# v3s-v0_1_1.net
KiCad netlist of a schematic drawn in EAGLE
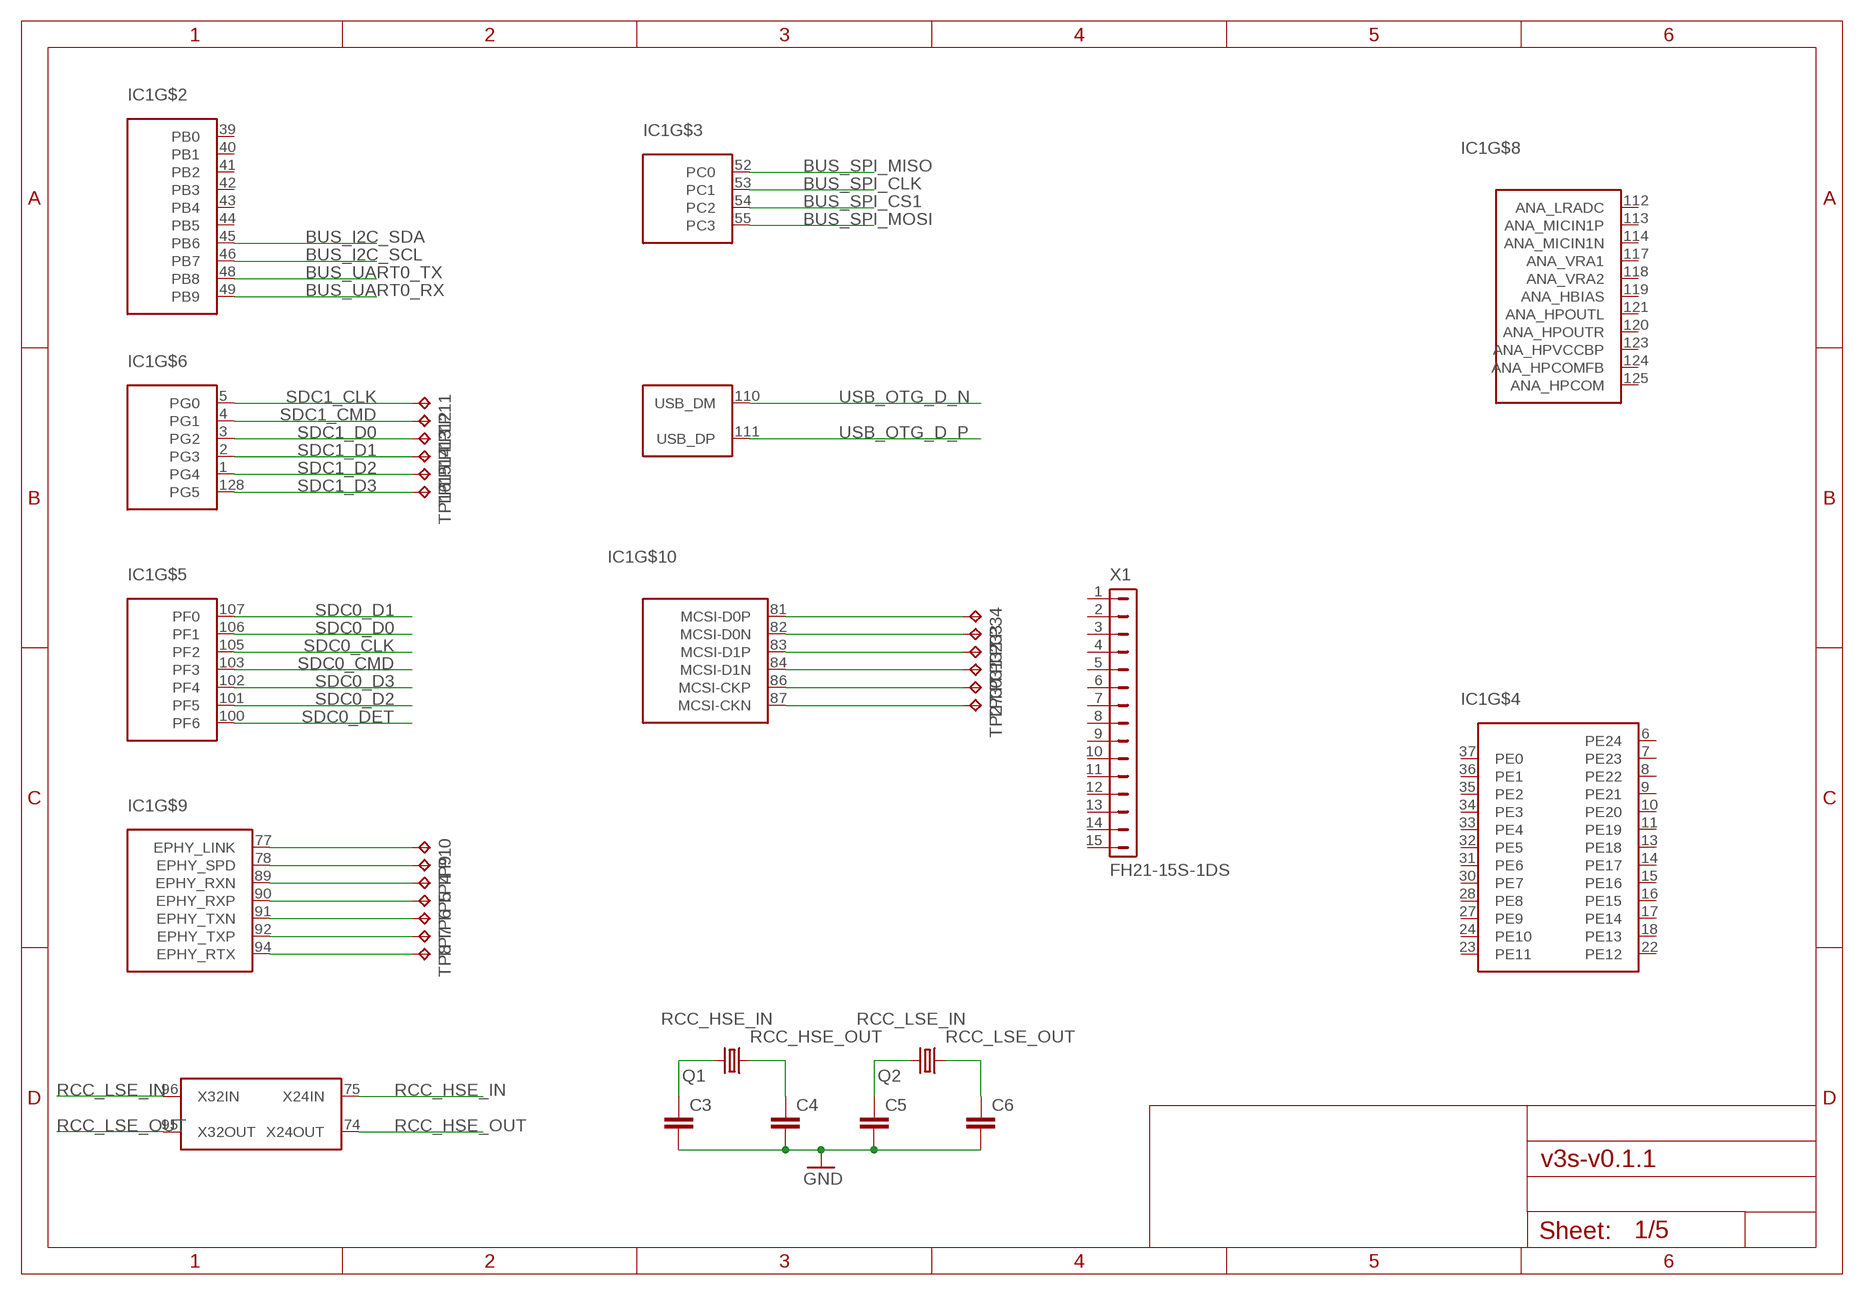
[diagram p0: schematic, sheet 1]
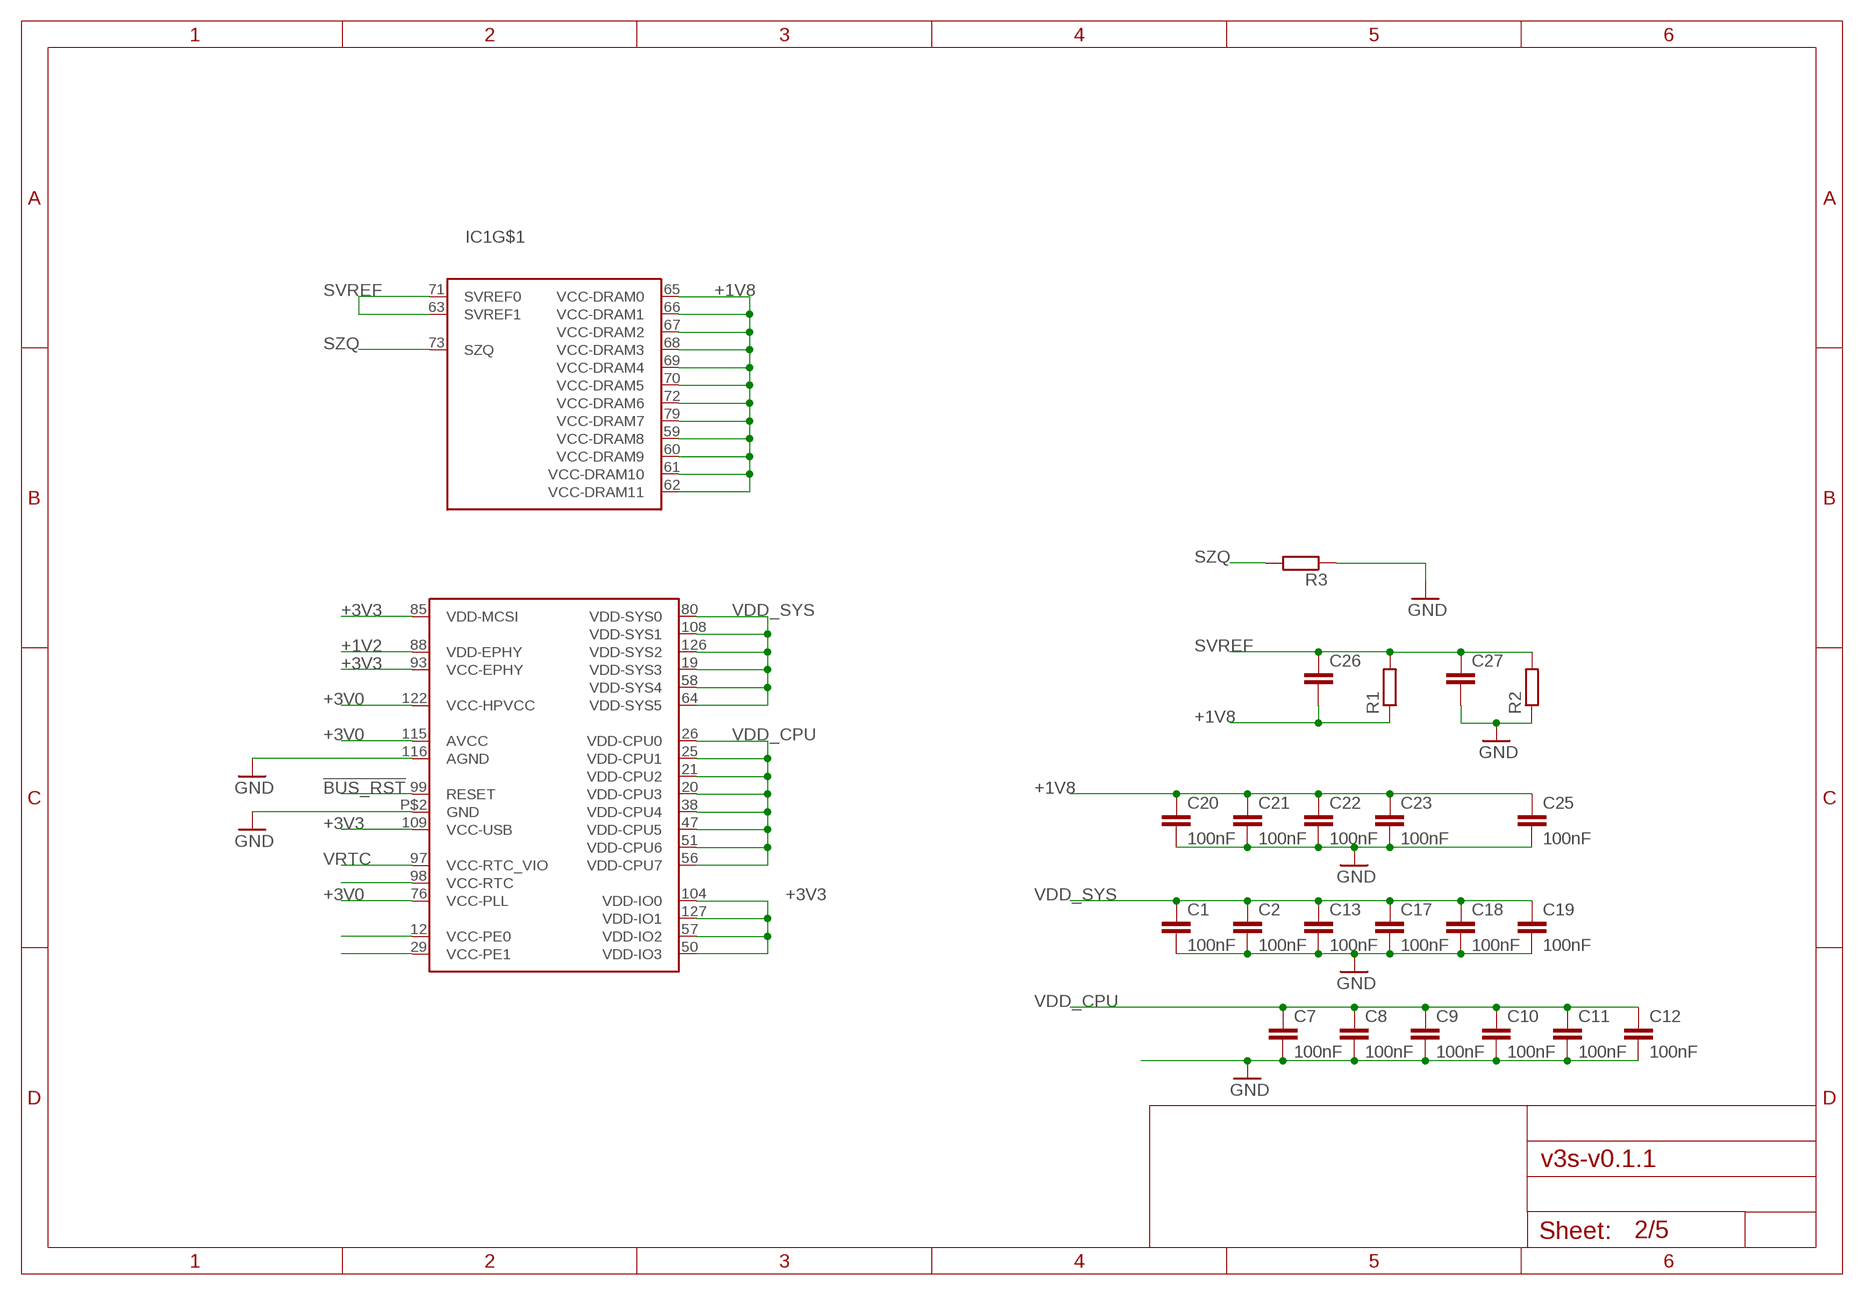
[diagram p1: schematic, sheet 2]
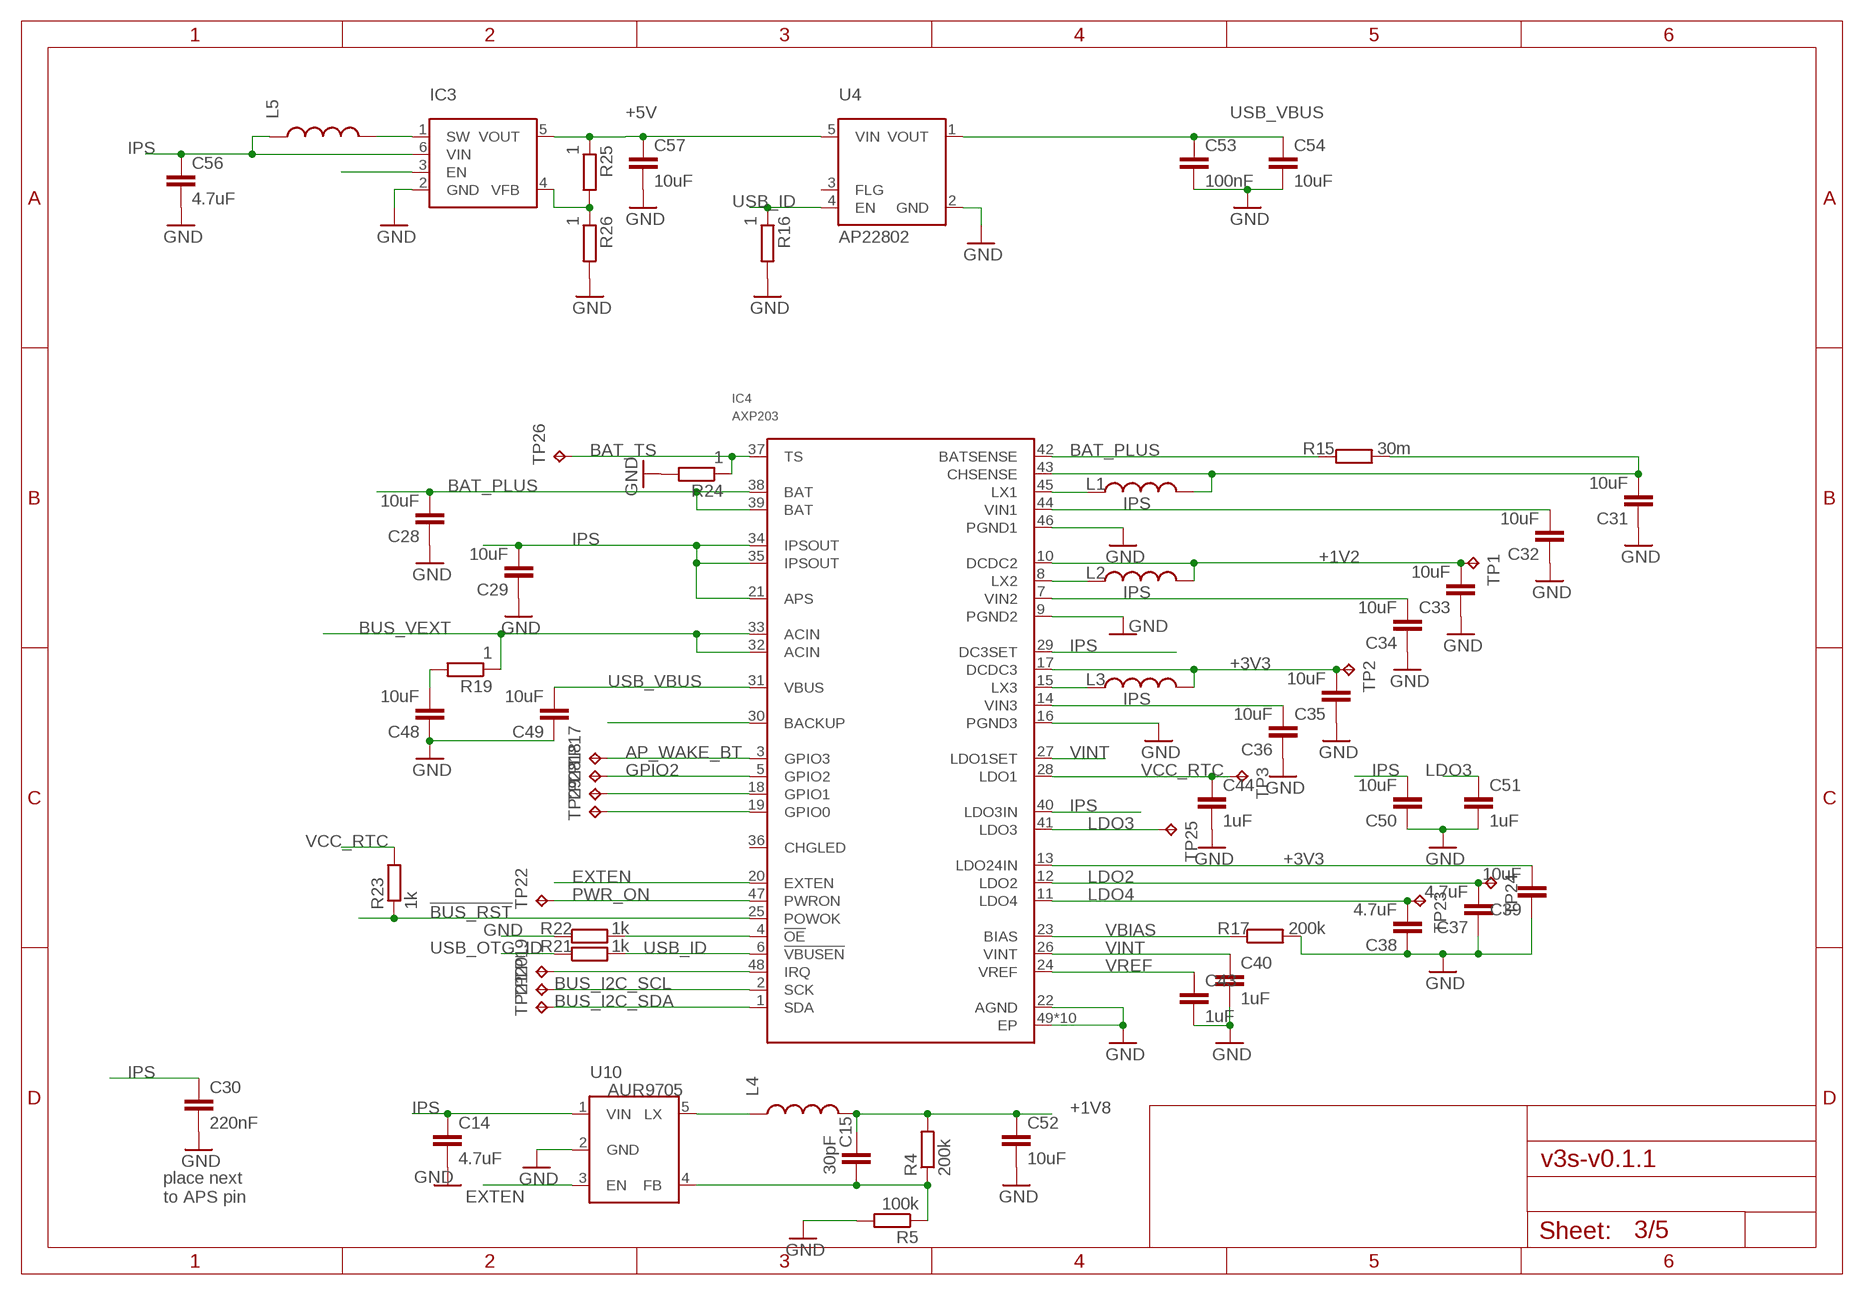
[diagram p2: schematic, sheet 3]
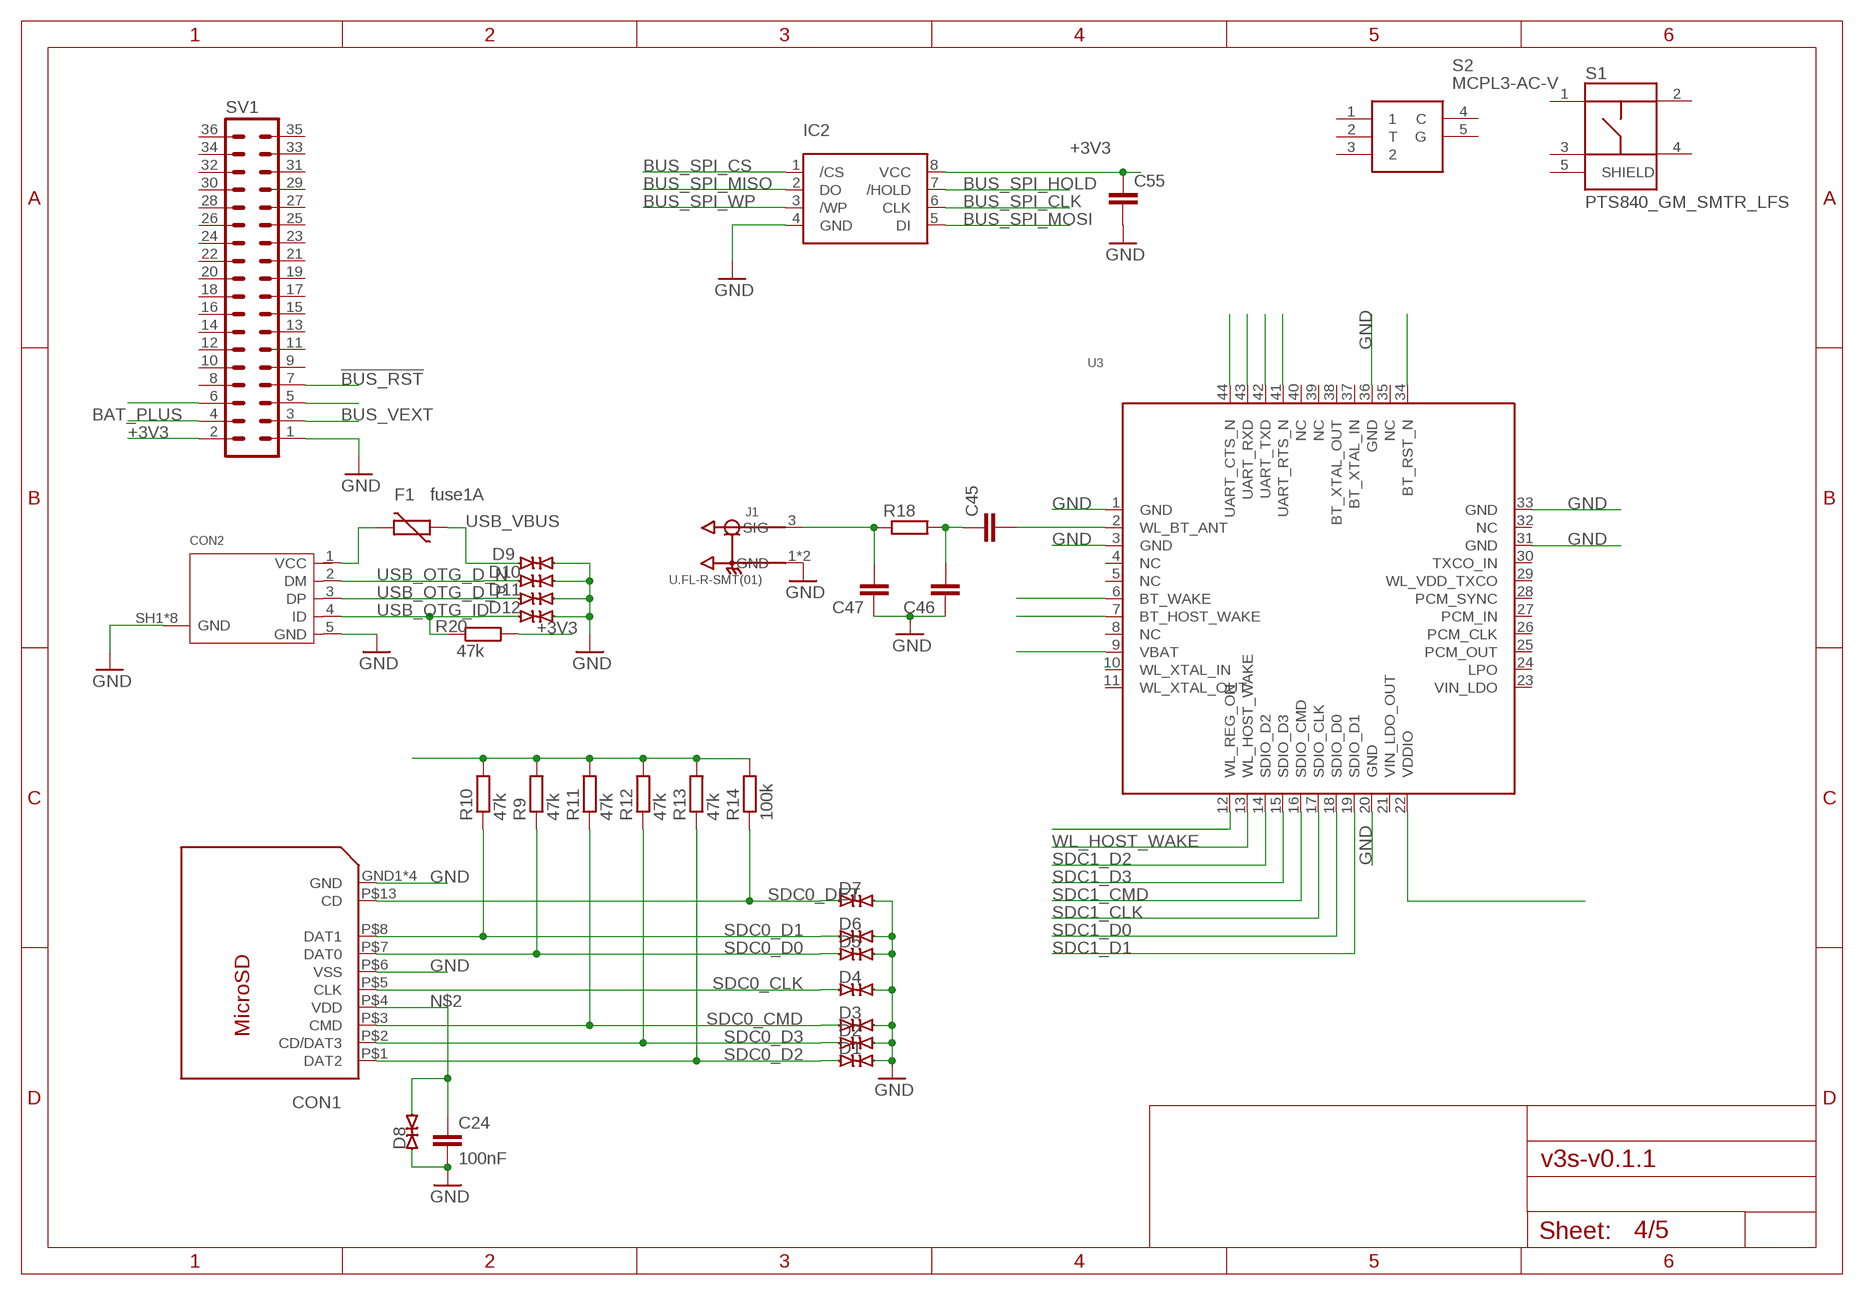
[diagram p3: schematic, sheet 4]
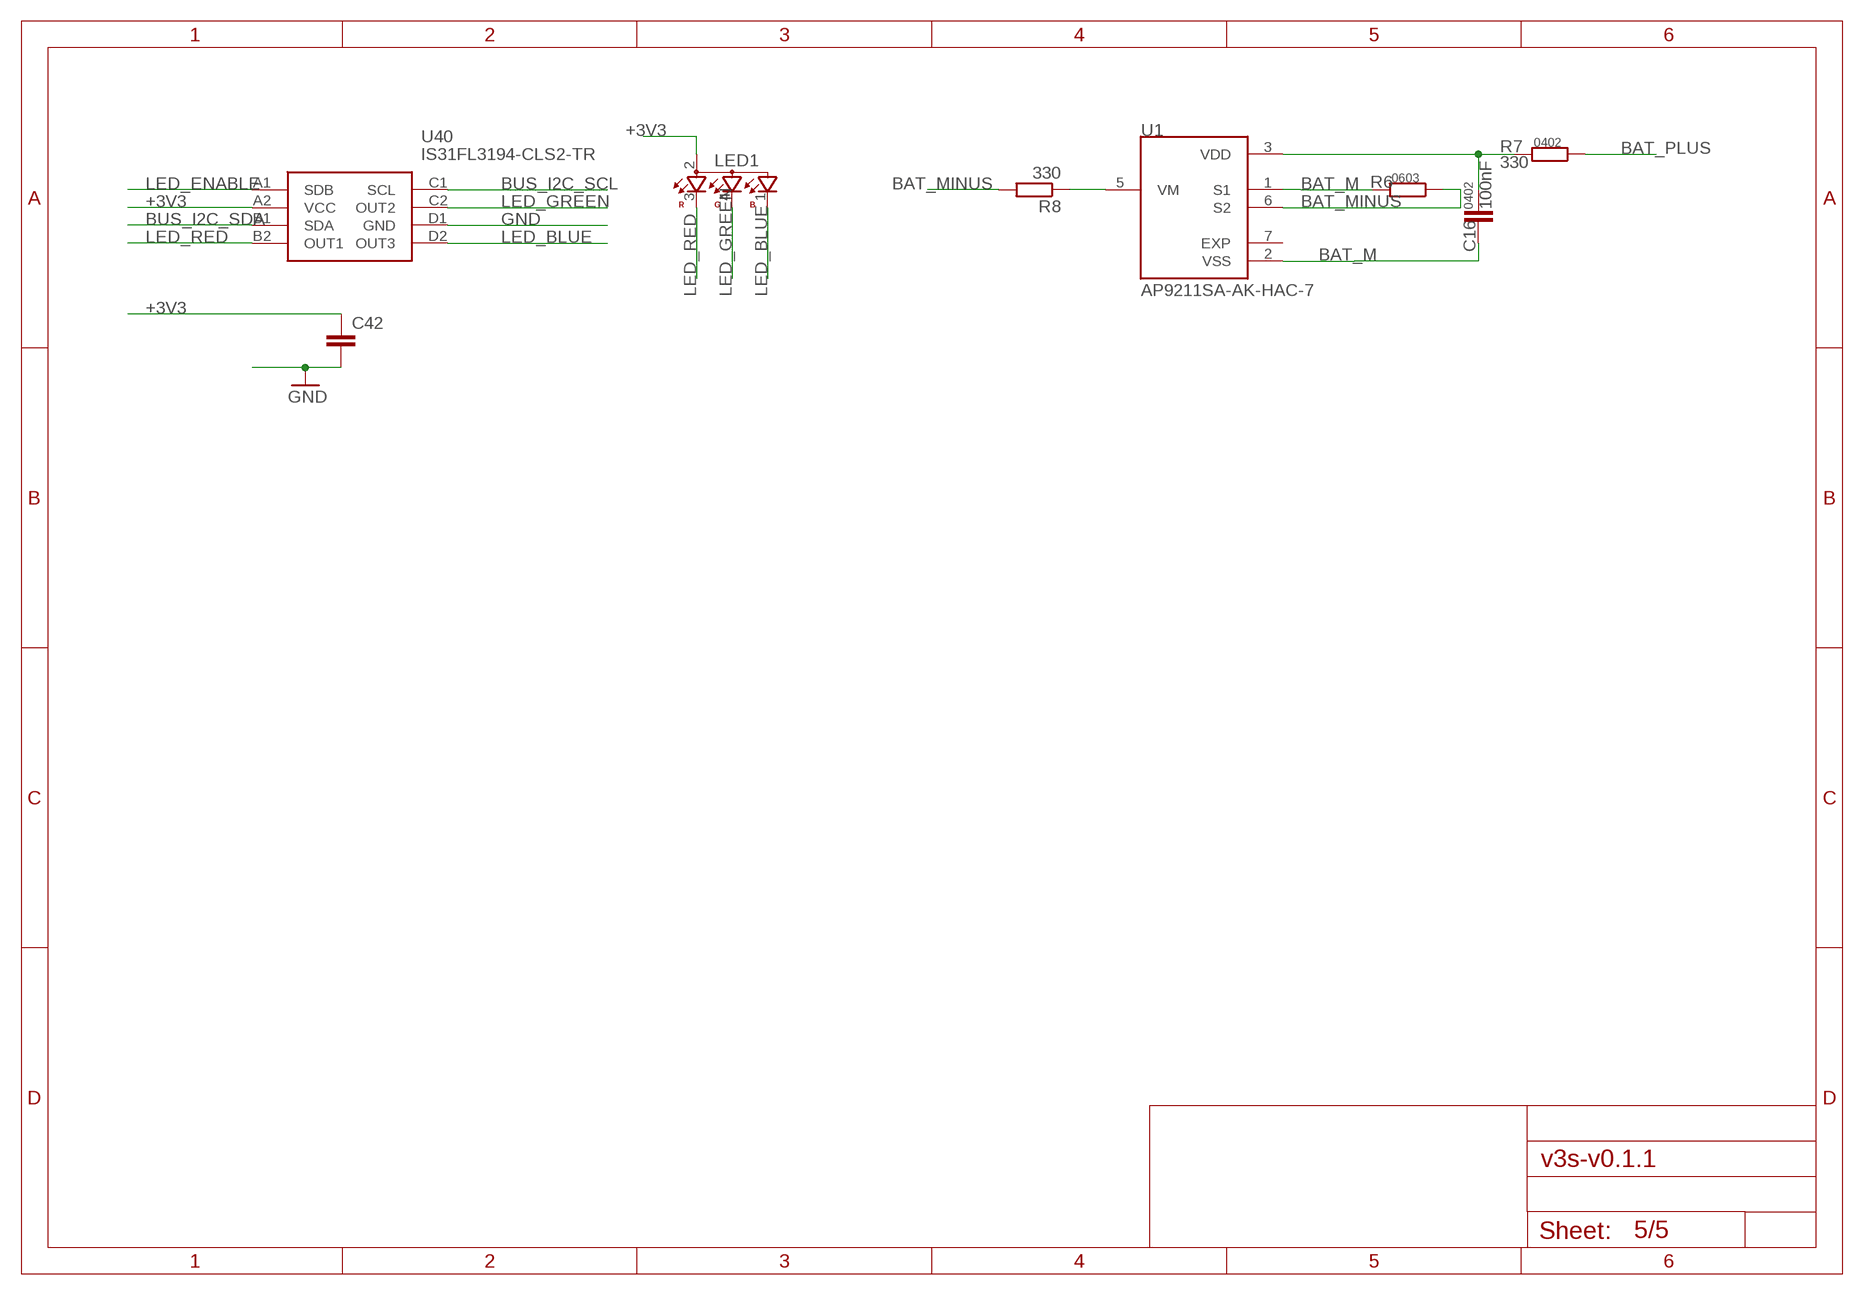
[diagram p4: schematic, sheet 5]

(export (version "E")
  (design (tool "Eeschema 10.0.6"))
  (components
    (comp (ref "C24")
      (value "100nF")
      (footprint "eagle-import:C0402")
      (libsource (lib "eagle-import") (part "C-EUC0402"))
    )
    (comp (ref "C45")
      (value "C-EUC0402")
      (footprint "eagle-import:C0402")
      (libsource (lib "eagle-import") (part "C-EUC0402"))
    )
    (comp (ref "C46")
      (value "C-EUC0402")
      (footprint "eagle-import:C0402")
      (libsource (lib "eagle-import") (part "C-EUC0402"))
    )
    (comp (ref "C47")
      (value "C-EUC0402")
      (footprint "eagle-import:C0402")
      (libsource (lib "eagle-import") (part "C-EUC0402"))
    )
    (comp (ref "C55")
      (value "C-EUC0603")
      (footprint "eagle-import:C0603")
      (libsource (lib "eagle-import") (part "C-EUC0603"))
    )
    (comp (ref "CON1")
      (value "112J-TXAR")
      (footprint "eagle-import:112J")
      (libsource (lib "eagle-import") (part "112J-TXAR"))
    )
    (comp (ref "CON2")
      (value "10118194-0001LF")
      (footprint "eagle-import:10118194")
      (libsource (lib "eagle-import") (part "10118194-0001LF"))
    )
    (comp (ref "D1")
      (value "ESD9B5.0ST5G")
      (footprint "eagle-import:SOD1006X40")
      (libsource (lib "eagle-import") (part "ESD9B5.0ST5G"))
    )
    (comp (ref "D2")
      (value "ESD9B5.0ST5G")
      (footprint "eagle-import:SOD1006X40")
      (libsource (lib "eagle-import") (part "ESD9B5.0ST5G"))
    )
    (comp (ref "D3")
      (value "ESD9B5.0ST5G")
      (footprint "eagle-import:SOD1006X40")
      (libsource (lib "eagle-import") (part "ESD9B5.0ST5G"))
    )
    (comp (ref "D4")
      (value "ESD9B5.0ST5G")
      (footprint "eagle-import:SOD1006X40")
      (libsource (lib "eagle-import") (part "ESD9B5.0ST5G"))
    )
    (comp (ref "D5")
      (value "ESD9B5.0ST5G")
      (footprint "eagle-import:SOD1006X40")
      (libsource (lib "eagle-import") (part "ESD9B5.0ST5G"))
    )
    (comp (ref "D6")
      (value "ESD9B5.0ST5G")
      (footprint "eagle-import:SOD1006X40")
      (libsource (lib "eagle-import") (part "ESD9B5.0ST5G"))
    )
    (comp (ref "D7")
      (value "ESD9B5.0ST5G")
      (footprint "eagle-import:SOD1006X40")
      (libsource (lib "eagle-import") (part "ESD9B5.0ST5G"))
    )
    (comp (ref "D8")
      (value "ESD9B5.0ST5G")
      (footprint "eagle-import:SOD1006X40")
      (libsource (lib "eagle-import") (part "ESD9B5.0ST5G"))
    )
    (comp (ref "D9")
      (value "ESD9B5.0ST5G")
      (footprint "eagle-import:SOD1006X40")
      (libsource (lib "eagle-import") (part "ESD9B5.0ST5G"))
    )
    (comp (ref "D10")
      (value "ESD9B5.0ST5G")
      (footprint "eagle-import:SOD1006X40")
      (libsource (lib "eagle-import") (part "ESD9B5.0ST5G"))
    )
    (comp (ref "D11")
      (value "ESD9B5.0ST5G")
      (footprint "eagle-import:SOD1006X40")
      (libsource (lib "eagle-import") (part "ESD9B5.0ST5G"))
    )
    (comp (ref "D12")
      (value "ESD9B5.0ST5G")
      (footprint "eagle-import:SOD1006X40")
      (libsource (lib "eagle-import") (part "ESD9B5.0ST5G"))
    )
    (comp (ref "F1")
      (value "fuse1A")
      (footprint "eagle-import:CT_CN0603")
      (libsource (lib "eagle-import") (part "VARISTORCN0603"))
    )
    (comp (ref "IC2")
      (value "W25Q128JV")
      (footprint "eagle-import:SO08-208")
      (libsource (lib "eagle-import") (part "W25Q128JV"))
    )
    (comp (ref "J1")
      (value "U.FL-R-SMT(01)")
      (footprint "eagle-import:HRS_U.FL-R-SMT(01)")
      (fields (field (name "MF") "Hirose") (field (name "MP") "U.FL-R-SMT_01_"))
      (libsource (lib "eagle-import") (part "U.FL-R-SMT(01)"))
    )
    (comp (ref "R9")
      (value "47k")
      (footprint "eagle-import:R0402")
      (libsource (lib "eagle-import") (part "R-EU_R0402"))
    )
    (comp (ref "R10")
      (value "47k")
      (footprint "eagle-import:R0402")
      (libsource (lib "eagle-import") (part "R-EU_R0402"))
    )
    (comp (ref "R11")
      (value "47k")
      (footprint "eagle-import:R0402")
      (libsource (lib "eagle-import") (part "R-EU_R0402"))
    )
    (comp (ref "R12")
      (value "47k")
      (footprint "eagle-import:R0402")
      (libsource (lib "eagle-import") (part "R-EU_R0402"))
    )
    (comp (ref "R13")
      (value "47k")
      (footprint "eagle-import:R0402")
      (libsource (lib "eagle-import") (part "R-EU_R0402"))
    )
    (comp (ref "R14")
      (value "100k")
      (footprint "eagle-import:R0402")
      (libsource (lib "eagle-import") (part "R-EU_R0402"))
    )
    (comp (ref "R18")
      (value "R-EU_R0402")
      (footprint "eagle-import:R0402")
      (libsource (lib "eagle-import") (part "R-EU_R0402"))
    )
    (comp (ref "R20")
      (value "47k")
      (footprint "eagle-import:R0402")
      (libsource (lib "eagle-import") (part "R-EU_R0402"))
    )
    (comp (ref "S1")
      (value "PTS840_GM_SMTR_LFS")
      (footprint "eagle-import:SW_PTS840GMSMTRLFS")
      (fields (field (name "MF") "C&K") (field (name "MP") "PTS840 GM SMTR LFS"))
      (libsource (lib "eagle-import") (part "PTS840_GM_SMTR_LFS"))
    )
    (comp (ref "S2")
      (value "MCPL3-AC-V")
      (footprint "eagle-import:MCPL3-AC-V")
      (libsource (lib "eagle-import") (part "MCPL3-AC-V"))
    )
    (comp (ref "SV1")
      (value "MA18-2")
      (footprint "eagle-import:MA18-2")
      (libsource (lib "eagle-import") (part "MA18-2"))
    )
    (comp (ref "U3")
      (value "RTL8723BS")
      (footprint "eagle-import:QFN90P1200X1200X100-44")
      (libsource (lib "eagle-import") (part "RTL8723BS"))
    )
    (comp (ref "C1")
      (value "100nF")
      (footprint "eagle-import:C0402")
      (libsource (lib "eagle-import") (part "C-EUC0402"))
    )
    (comp (ref "C2")
      (value "100nF")
      (footprint "eagle-import:C0402")
      (libsource (lib "eagle-import") (part "C-EUC0402"))
    )
    (comp (ref "C7")
      (value "100nF")
      (footprint "eagle-import:C0402")
      (libsource (lib "eagle-import") (part "C-EUC0402"))
    )
    (comp (ref "C8")
      (value "100nF")
      (footprint "eagle-import:C0402")
      (libsource (lib "eagle-import") (part "C-EUC0402"))
    )
    (comp (ref "C9")
      (value "100nF")
      (footprint "eagle-import:C0402")
      (libsource (lib "eagle-import") (part "C-EUC0402"))
    )
    (comp (ref "C10")
      (value "100nF")
      (footprint "eagle-import:C0402")
      (libsource (lib "eagle-import") (part "C-EUC0402"))
    )
    (comp (ref "C11")
      (value "100nF")
      (footprint "eagle-import:C0402")
      (libsource (lib "eagle-import") (part "C-EUC0402"))
    )
    (comp (ref "C12")
      (value "100nF")
      (footprint "eagle-import:C0402")
      (libsource (lib "eagle-import") (part "C-EUC0402"))
    )
    (comp (ref "C13")
      (value "100nF")
      (footprint "eagle-import:C0402")
      (libsource (lib "eagle-import") (part "C-EUC0402"))
    )
    (comp (ref "C17")
      (value "100nF")
      (footprint "eagle-import:C0402")
      (libsource (lib "eagle-import") (part "C-EUC0402"))
    )
    (comp (ref "C18")
      (value "100nF")
      (footprint "eagle-import:C0402")
      (libsource (lib "eagle-import") (part "C-EUC0402"))
    )
    (comp (ref "C19")
      (value "100nF")
      (footprint "eagle-import:C0402")
      (libsource (lib "eagle-import") (part "C-EUC0402"))
    )
    (comp (ref "C20")
      (value "100nF")
      (footprint "eagle-import:C0402")
      (libsource (lib "eagle-import") (part "C-EUC0402"))
    )
    (comp (ref "C21")
      (value "100nF")
      (footprint "eagle-import:C0402")
      (libsource (lib "eagle-import") (part "C-EUC0402"))
    )
    (comp (ref "C22")
      (value "100nF")
      (footprint "eagle-import:C0402")
      (libsource (lib "eagle-import") (part "C-EUC0402"))
    )
    (comp (ref "C23")
      (value "100nF")
      (footprint "eagle-import:C0402")
      (libsource (lib "eagle-import") (part "C-EUC0402"))
    )
    (comp (ref "C25")
      (value "100nF")
      (footprint "eagle-import:C0402")
      (libsource (lib "eagle-import") (part "C-EUC0402"))
    )
    (comp (ref "C26")
      (value "C-EUC0402")
      (footprint "eagle-import:C0402")
      (libsource (lib "eagle-import") (part "C-EUC0402"))
    )
    (comp (ref "C27")
      (value "C-EUC0402")
      (footprint "eagle-import:C0402")
      (libsource (lib "eagle-import") (part "C-EUC0402"))
    )
    (comp (ref "IC1")
      (value "V3S")
      (footprint "eagle-import:QFP-128")
      (libsource (lib "eagle-import") (part "V3S"))
    )
    (comp (ref "R1")
      (value "R-EU_R0402")
      (footprint "eagle-import:R0402")
      (libsource (lib "eagle-import") (part "R-EU_R0402"))
    )
    (comp (ref "R2")
      (value "R-EU_R0402")
      (footprint "eagle-import:R0402")
      (libsource (lib "eagle-import") (part "R-EU_R0402"))
    )
    (comp (ref "R3")
      (value "R-EU_R0402")
      (footprint "eagle-import:R0402")
      (libsource (lib "eagle-import") (part "R-EU_R0402"))
    )
    (comp (ref "C16")
      (value "100nF")
      (footprint "eagle-import:C0402")
      (libsource (lib "eagle-import") (part "C-EUC0402"))
    )
    (comp (ref "C42")
      (value "C-EUC0402")
      (footprint "eagle-import:C0402")
      (libsource (lib "eagle-import") (part "C-EUC0402"))
    )
    (comp (ref "LED1")
      (value "OSTB1204C1E")
      (footprint "eagle-import:321015RGB")
      (libsource (lib "eagle-import") (part "OSTB1204C1E"))
    )
    (comp (ref "R6")
      (value "R-EU_R0603")
      (footprint "eagle-import:R0603")
      (libsource (lib "eagle-import") (part "R-EU_R0603"))
    )
    (comp (ref "R7")
      (value "330")
      (footprint "eagle-import:R0402")
      (libsource (lib "eagle-import") (part "R-EU_R0402"))
    )
    (comp (ref "R8")
      (value "330")
      (footprint "eagle-import:R0402")
      (libsource (lib "eagle-import") (part "R-EU_R0402"))
    )
    (comp (ref "U1")
      (value "AP9211SA-AK-HAC-7")
      (footprint "eagle-import:DFN200X300X60-7N")
      (fields (field (name "MF") "Diodes Inc."))
      (libsource (lib "eagle-import") (part "AP9211SA-AK-HAC-7"))
    )
    (comp (ref "U40")
      (value "IS31FL3194-CLS2-TR")
      (footprint "eagle-import:BGA8C40P2X4_99X159X42")
      (fields (field (name "MOUSER_PART_NUMBER") "870-IS31FL3194CLS2TR"))
      (libsource (lib "eagle-import") (part "IS31FL3194-CLS2-TR"))
    )
    (comp (ref "C3")
      (value "C-EUC0402")
      (footprint "eagle-import:C0402")
      (libsource (lib "eagle-import") (part "C-EUC0402"))
    )
    (comp (ref "C4")
      (value "C-EUC0402")
      (footprint "eagle-import:C0402")
      (libsource (lib "eagle-import") (part "C-EUC0402"))
    )
    (comp (ref "C5")
      (value "C-EUC0402")
      (footprint "eagle-import:C0402")
      (libsource (lib "eagle-import") (part "C-EUC0402"))
    )
    (comp (ref "C6")
      (value "C-EUC0402")
      (footprint "eagle-import:C0402")
      (libsource (lib "eagle-import") (part "C-EUC0402"))
    )
    (comp (ref "Q1")
      (value "KX-7")
      (footprint "eagle-import:3.2X2.5_KX-7")
      (libsource (lib "eagle-import") (part "KX-7"))
    )
    (comp (ref "Q2")
      (value "KX-327-NHF")
      (footprint "eagle-import:3.2X1.5")
      (libsource (lib "eagle-import") (part "KX-327-NHF"))
    )
    (comp (ref "TP4")
      (value "TPB1,27")
      (footprint "eagle-import:B1,27")
      (libsource (lib "eagle-import") (part "TPB1,27"))
    )
    (comp (ref "TP5")
      (value "TPB1,27")
      (footprint "eagle-import:B1,27")
      (libsource (lib "eagle-import") (part "TPB1,27"))
    )
    (comp (ref "TP6")
      (value "TPB1,27")
      (footprint "eagle-import:B1,27")
      (libsource (lib "eagle-import") (part "TPB1,27"))
    )
    (comp (ref "TP7")
      (value "TPB1,27")
      (footprint "eagle-import:B1,27")
      (libsource (lib "eagle-import") (part "TPB1,27"))
    )
    (comp (ref "TP8")
      (value "TPB1,27")
      (footprint "eagle-import:B1,27")
      (libsource (lib "eagle-import") (part "TPB1,27"))
    )
    (comp (ref "TP9")
      (value "TPB1,27")
      (footprint "eagle-import:B1,27")
      (libsource (lib "eagle-import") (part "TPB1,27"))
    )
    (comp (ref "TP10")
      (value "TPB1,27")
      (footprint "eagle-import:B1,27")
      (libsource (lib "eagle-import") (part "TPB1,27"))
    )
    (comp (ref "TP11")
      (value "TPB1,27")
      (footprint "eagle-import:B1,27")
      (libsource (lib "eagle-import") (part "TPB1,27"))
    )
    (comp (ref "TP12")
      (value "TPB1,27")
      (footprint "eagle-import:B1,27")
      (libsource (lib "eagle-import") (part "TPB1,27"))
    )
    (comp (ref "TP13")
      (value "TPB1,27")
      (footprint "eagle-import:B1,27")
      (libsource (lib "eagle-import") (part "TPB1,27"))
    )
    (comp (ref "TP14")
      (value "TPB1,27")
      (footprint "eagle-import:B1,27")
      (libsource (lib "eagle-import") (part "TPB1,27"))
    )
    (comp (ref "TP15")
      (value "TPB1,27")
      (footprint "eagle-import:B1,27")
      (libsource (lib "eagle-import") (part "TPB1,27"))
    )
    (comp (ref "TP16")
      (value "TPB1,27")
      (footprint "eagle-import:B1,27")
      (libsource (lib "eagle-import") (part "TPB1,27"))
    )
    (comp (ref "TP27")
      (value "TPB1,27")
      (footprint "eagle-import:B1,27")
      (libsource (lib "eagle-import") (part "TPB1,27"))
    )
    (comp (ref "TP30")
      (value "TPB1,27")
      (footprint "eagle-import:B1,27")
      (libsource (lib "eagle-import") (part "TPB1,27"))
    )
    (comp (ref "TP31")
      (value "TPB1,27")
      (footprint "eagle-import:B1,27")
      (libsource (lib "eagle-import") (part "TPB1,27"))
    )
    (comp (ref "TP32")
      (value "TPB1,27")
      (footprint "eagle-import:B1,27")
      (libsource (lib "eagle-import") (part "TPB1,27"))
    )
    (comp (ref "TP33")
      (value "TPB1,27")
      (footprint "eagle-import:B1,27")
      (libsource (lib "eagle-import") (part "TPB1,27"))
    )
    (comp (ref "TP34")
      (value "TPB1,27")
      (footprint "eagle-import:B1,27")
      (libsource (lib "eagle-import") (part "TPB1,27"))
    )
    (comp (ref "X1")
      (value "FH21-15S-1DS")
      (footprint "eagle-import:FH21-15S-1DS")
      (libsource (lib "eagle-import") (part "FH21-15S-1DS"))
    )
    (comp (ref "C14")
      (value "4.7uF")
      (footprint "eagle-import:C0603")
      (libsource (lib "eagle-import") (part "C-EUC0603"))
    )
    (comp (ref "C15")
      (value "30pF")
      (footprint "eagle-import:C0402")
      (libsource (lib "eagle-import") (part "C-EUC0402"))
    )
    (comp (ref "C28")
      (value "10uF")
      (footprint "eagle-import:C0603")
      (libsource (lib "eagle-import") (part "C-EUC0603"))
    )
    (comp (ref "C29")
      (value "10uF")
      (footprint "eagle-import:C0603")
      (libsource (lib "eagle-import") (part "C-EUC0603"))
    )
    (comp (ref "C30")
      (value "220nF")
      (footprint "eagle-import:C0402")
      (libsource (lib "eagle-import") (part "C-EUC0402"))
    )
    (comp (ref "C31")
      (value "10uF")
      (footprint "eagle-import:C0603")
      (libsource (lib "eagle-import") (part "C-EUC0603"))
    )
    (comp (ref "C32")
      (value "10uF")
      (footprint "eagle-import:C0603")
      (libsource (lib "eagle-import") (part "C-EUC0603"))
    )
    (comp (ref "C33")
      (value "10uF")
      (footprint "eagle-import:C0603")
      (libsource (lib "eagle-import") (part "C-EUC0603"))
    )
    (comp (ref "C34")
      (value "10uF")
      (footprint "eagle-import:C0603")
      (libsource (lib "eagle-import") (part "C-EUC0603"))
    )
    (comp (ref "C35")
      (value "10uF")
      (footprint "eagle-import:C0603")
      (libsource (lib "eagle-import") (part "C-EUC0603"))
    )
    (comp (ref "C36")
      (value "10uF")
      (footprint "eagle-import:C0603")
      (libsource (lib "eagle-import") (part "C-EUC0603"))
    )
    (comp (ref "C37")
      (value "4.7uF")
      (footprint "eagle-import:C0603")
      (libsource (lib "eagle-import") (part "C-EUC0603"))
    )
    (comp (ref "C38")
      (value "4.7uF")
      (footprint "eagle-import:C0603")
      (libsource (lib "eagle-import") (part "C-EUC0603"))
    )
    (comp (ref "C39")
      (value "10uF")
      (footprint "eagle-import:C0603")
      (libsource (lib "eagle-import") (part "C-EUC0603"))
    )
    (comp (ref "C40")
      (value "1uF")
      (footprint "eagle-import:C0402")
      (libsource (lib "eagle-import") (part "C-EUC0402"))
    )
    (comp (ref "C43")
      (value "1uF")
      (footprint "eagle-import:C0402")
      (libsource (lib "eagle-import") (part "C-EUC0402"))
    )
    (comp (ref "C44")
      (value "1uF")
      (footprint "eagle-import:C0402")
      (libsource (lib "eagle-import") (part "C-EUC0402"))
    )
    (comp (ref "C48")
      (value "10uF")
      (footprint "eagle-import:C0603")
      (libsource (lib "eagle-import") (part "C-EUC0603"))
    )
    (comp (ref "C49")
      (value "10uF")
      (footprint "eagle-import:C0603")
      (libsource (lib "eagle-import") (part "C-EUC0603"))
    )
    (comp (ref "C50")
      (value "10uF")
      (footprint "eagle-import:C0603")
      (libsource (lib "eagle-import") (part "C-EUC0603"))
    )
    (comp (ref "C51")
      (value "1uF")
      (footprint "eagle-import:C0402")
      (libsource (lib "eagle-import") (part "C-EUC0402"))
    )
    (comp (ref "C52")
      (value "10uF")
      (footprint "eagle-import:C0603")
      (libsource (lib "eagle-import") (part "C-EUC0603"))
    )
    (comp (ref "C53")
      (value "100nF")
      (footprint "eagle-import:C0402")
      (libsource (lib "eagle-import") (part "C-EUC0402"))
    )
    (comp (ref "C54")
      (value "10uF")
      (footprint "eagle-import:C0603")
      (libsource (lib "eagle-import") (part "C-EUC0603"))
    )
    (comp (ref "C56")
      (value "4.7uF")
      (footprint "eagle-import:C0603")
      (libsource (lib "eagle-import") (part "C-EUC0603"))
    )
    (comp (ref "C57")
      (value "10uF")
      (footprint "eagle-import:C0603")
      (libsource (lib "eagle-import") (part "C-EUC0603"))
    )
    (comp (ref "IC3")
      (value "MCP1640")
      (footprint "eagle-import:SOT95P280X110-6")
      (libsource (lib "eagle-import") (part "MCP1640"))
    )
    (comp (ref "IC4")
      (value "AXP203")
      (footprint "eagle-import:QFN40P600X600X80-49T405")
      (libsource (lib "eagle-import") (part "AXP203"))
    )
    (comp (ref "L1")
      (value "DJNR3015")
      (footprint "eagle-import:L3230M")
      (libsource (lib "eagle-import") (part "DJNR3015"))
    )
    (comp (ref "L2")
      (value "DJNR3015")
      (footprint "eagle-import:L3230M")
      (libsource (lib "eagle-import") (part "DJNR3015"))
    )
    (comp (ref "L3")
      (value "DJNR3015")
      (footprint "eagle-import:L3230M")
      (libsource (lib "eagle-import") (part "DJNR3015"))
    )
    (comp (ref "L4")
      (value "DJNR3015")
      (footprint "eagle-import:L3230M")
      (libsource (lib "eagle-import") (part "DJNR3015"))
    )
    (comp (ref "L5")
      (value "DJNR3015")
      (footprint "eagle-import:L3230M")
      (libsource (lib "eagle-import") (part "DJNR3015"))
    )
    (comp (ref "R4")
      (value "200k")
      (footprint "eagle-import:R0402")
      (libsource (lib "eagle-import") (part "R-EU_R0402"))
    )
    (comp (ref "R5")
      (value "100k")
      (footprint "eagle-import:R0402")
      (libsource (lib "eagle-import") (part "R-EU_R0402"))
    )
    (comp (ref "R15")
      (value "30m")
      (footprint "eagle-import:R0805")
      (libsource (lib "eagle-import") (part "R-EU_R0805"))
    )
    (comp (ref "R16")
      (value "1")
      (footprint "eagle-import:R0402")
      (libsource (lib "eagle-import") (part "R-EU_R0402"))
    )
    (comp (ref "R17")
      (value "200k")
      (footprint "eagle-import:R0402")
      (libsource (lib "eagle-import") (part "R-EU_R0402"))
    )
    (comp (ref "R19")
      (value "1")
      (footprint "eagle-import:R0402")
      (libsource (lib "eagle-import") (part "R-EU_R0402"))
    )
    (comp (ref "R21")
      (value "1k")
      (footprint "eagle-import:R0402")
      (libsource (lib "eagle-import") (part "R-EU_R0402"))
    )
    (comp (ref "R22")
      (value "1k")
      (footprint "eagle-import:R0402")
      (libsource (lib "eagle-import") (part "R-EU_R0402"))
    )
    (comp (ref "R23")
      (value "1k")
      (footprint "eagle-import:R0402")
      (libsource (lib "eagle-import") (part "R-EU_R0402"))
    )
    (comp (ref "R24")
      (value "1")
      (footprint "eagle-import:R0402")
      (libsource (lib "eagle-import") (part "R-EU_R0402"))
    )
    (comp (ref "R25")
      (value "1")
      (footprint "eagle-import:R0402")
      (libsource (lib "eagle-import") (part "R-EU_R0402"))
    )
    (comp (ref "R26")
      (value "1")
      (footprint "eagle-import:R0402")
      (libsource (lib "eagle-import") (part "R-EU_R0402"))
    )
    (comp (ref "TP1")
      (value "TPB1,27")
      (footprint "eagle-import:B1,27")
      (libsource (lib "eagle-import") (part "TPB1,27"))
    )
    (comp (ref "TP2")
      (value "TPB1,27")
      (footprint "eagle-import:B1,27")
      (libsource (lib "eagle-import") (part "TPB1,27"))
    )
    (comp (ref "TP3")
      (value "TPB1,27")
      (footprint "eagle-import:B1,27")
      (libsource (lib "eagle-import") (part "TPB1,27"))
    )
    (comp (ref "TP17")
      (value "TPB1,27")
      (footprint "eagle-import:B1,27")
      (libsource (lib "eagle-import") (part "TPB1,27"))
    )
    (comp (ref "TP18")
      (value "TPB1,27")
      (footprint "eagle-import:B1,27")
      (libsource (lib "eagle-import") (part "TPB1,27"))
    )
    (comp (ref "TP19")
      (value "TPB1,27")
      (footprint "eagle-import:B1,27")
      (libsource (lib "eagle-import") (part "TPB1,27"))
    )
    (comp (ref "TP20")
      (value "TPB1,27")
      (footprint "eagle-import:B1,27")
      (libsource (lib "eagle-import") (part "TPB1,27"))
    )
    (comp (ref "TP21")
      (value "TPB1,27")
      (footprint "eagle-import:B1,27")
      (libsource (lib "eagle-import") (part "TPB1,27"))
    )
    (comp (ref "TP22")
      (value "TPB1,27")
      (footprint "eagle-import:B1,27")
      (libsource (lib "eagle-import") (part "TPB1,27"))
    )
    (comp (ref "TP23")
      (value "TPB1,27")
      (footprint "eagle-import:B1,27")
      (libsource (lib "eagle-import") (part "TPB1,27"))
    )
    (comp (ref "TP24")
      (value "TPB1,27")
      (footprint "eagle-import:B1,27")
      (libsource (lib "eagle-import") (part "TPB1,27"))
    )
    (comp (ref "TP25")
      (value "TPB1,27")
      (footprint "eagle-import:B1,27")
      (libsource (lib "eagle-import") (part "TPB1,27"))
    )
    (comp (ref "TP26")
      (value "TPB1,27")
      (footprint "eagle-import:B1,27")
      (libsource (lib "eagle-import") (part "TPB1,27"))
    )
    (comp (ref "TP28")
      (value "TPB1,27")
      (footprint "eagle-import:B1,27")
      (libsource (lib "eagle-import") (part "TPB1,27"))
    )
    (comp (ref "TP29")
      (value "TPB1,27")
      (footprint "eagle-import:B1,27")
      (libsource (lib "eagle-import") (part "TPB1,27"))
    )
    (comp (ref "U4")
      (value "AP22802")
      (footprint "eagle-import:SOT25")
      (libsource (lib "eagle-import") (part "AP22802"))
    )
    (comp (ref "U10")
      (value "AUR9705")
      (footprint "eagle-import:SOT25")
      (libsource (lib "eagle-import") (part "AUR9705"))
    )
  )
  (nets
    (net (code "1") (name "+1V2") (class "Default")
      (node (ref "C33") (pin "2") (pinfunction "2_2") (pintype "passive"))
      (node (ref "IC1") (pin "88") (pinfunction "VDD-EPHY_88") (pintype "bidirectional"))
      (node (ref "IC4") (pin "10") (pinfunction "DCDC2_10") (pintype "bidirectional"))
      (node (ref "L2") (pin "2") (pinfunction "2_2") (pintype "passive"))
      (node (ref "TP1") (pin "TP") (pinfunction "TP_TP") (pintype "input"))
    )
    (net (code "2") (name "+1V8") (class "Default")
      (node (ref "C15") (pin "1") (pinfunction "1_1") (pintype "passive"))
      (node (ref "C20") (pin "1") (pinfunction "1_1") (pintype "passive"))
      (node (ref "C21") (pin "1") (pinfunction "1_1") (pintype "passive"))
      (node (ref "C22") (pin "1") (pinfunction "1_1") (pintype "passive"))
      (node (ref "C23") (pin "1") (pinfunction "1_1") (pintype "passive"))
      (node (ref "C25") (pin "1") (pinfunction "1_1") (pintype "passive"))
      (node (ref "C26") (pin "2") (pinfunction "2_2") (pintype "passive"))
      (node (ref "C52") (pin "1") (pinfunction "1_1") (pintype "passive"))
      (node (ref "IC1") (pin "59") (pinfunction "VCC-DRAM8_59") (pintype "bidirectional"))
      (node (ref "IC1") (pin "60") (pinfunction "VCC-DRAM9_60") (pintype "bidirectional"))
      (node (ref "IC1") (pin "61") (pinfunction "VCC-DRAM10_61") (pintype "bidirectional"))
      (node (ref "IC1") (pin "62") (pinfunction "VCC-DRAM11_62") (pintype "bidirectional"))
      (node (ref "IC1") (pin "65") (pinfunction "VCC-DRAM0_65") (pintype "bidirectional"))
      (node (ref "IC1") (pin "66") (pinfunction "VCC-DRAM1_66") (pintype "bidirectional"))
      (node (ref "IC1") (pin "67") (pinfunction "VCC-DRAM2_67") (pintype "bidirectional"))
      (node (ref "IC1") (pin "68") (pinfunction "VCC-DRAM3_68") (pintype "bidirectional"))
      (node (ref "IC1") (pin "69") (pinfunction "VCC-DRAM4_69") (pintype "bidirectional"))
      (node (ref "IC1") (pin "70") (pinfunction "VCC-DRAM5_70") (pintype "bidirectional"))
      (node (ref "IC1") (pin "72") (pinfunction "VCC-DRAM6_72") (pintype "bidirectional"))
      (node (ref "IC1") (pin "79") (pinfunction "VCC-DRAM7_79") (pintype "bidirectional"))
      (node (ref "L4") (pin "2") (pinfunction "2_2") (pintype "passive"))
      (node (ref "R1") (pin "1") (pinfunction "1_1") (pintype "passive"))
      (node (ref "R4") (pin "2") (pinfunction "2_2") (pintype "passive"))
    )
    (net (code "3") (name "+3V0") (class "Default")
      (node (ref "IC1") (pin "115") (pinfunction "AVCC_115") (pintype "bidirectional"))
      (node (ref "IC1") (pin "122") (pinfunction "VCC-HPVCC_122") (pintype "bidirectional"))
      (node (ref "IC1") (pin "76") (pinfunction "VCC-PLL_76") (pintype "bidirectional"))
    )
    (net (code "4") (name "+3V3") (class "Default")
      (node (ref "C35") (pin "2") (pinfunction "2_2") (pintype "passive"))
      (node (ref "C39") (pin "2") (pinfunction "2_2") (pintype "passive"))
      (node (ref "C42") (pin "1") (pinfunction "1_1") (pintype "passive"))
      (node (ref "C55") (pin "1") (pinfunction "1_1") (pintype "passive"))
      (node (ref "IC1") (pin "104") (pinfunction "VDD-IO0_104") (pintype "bidirectional"))
      (node (ref "IC1") (pin "109") (pinfunction "VCC-USB_109") (pintype "bidirectional"))
      (node (ref "IC1") (pin "127") (pinfunction "VDD-IO1_127") (pintype "bidirectional"))
      (node (ref "IC1") (pin "50") (pinfunction "VDD-IO3_50") (pintype "bidirectional"))
      (node (ref "IC1") (pin "57") (pinfunction "VDD-IO2_57") (pintype "bidirectional"))
      (node (ref "IC1") (pin "85") (pinfunction "VDD-MCSI_85") (pintype "bidirectional"))
      (node (ref "IC1") (pin "93") (pinfunction "VCC-EPHY_93") (pintype "bidirectional"))
      (node (ref "IC2") (pin "8") (pinfunction "VCC_8") (pintype "bidirectional"))
      (node (ref "IC4") (pin "13") (pinfunction "LDO24IN_13") (pintype "bidirectional"))
      (node (ref "IC4") (pin "17") (pinfunction "DCDC3_17") (pintype "bidirectional"))
      (node (ref "L3") (pin "2") (pinfunction "2_2") (pintype "passive"))
      (node (ref "LED1") (pin "2") (pinfunction "2_2") (pintype "passive"))
      (node (ref "R20") (pin "2") (pinfunction "2_2") (pintype "passive"))
      (node (ref "SV1") (pin "2") (pinfunction "2_2") (pintype "passive"))
      (node (ref "TP2") (pin "TP") (pinfunction "TP_TP") (pintype "input"))
      (node (ref "U40") (pin "A2") (pinfunction "VCC_A2") (pintype "bidirectional"))
    )
    (net (code "5") (name "+5V") (class "Default")
      (node (ref "C57") (pin "1") (pinfunction "1_1") (pintype "passive"))
      (node (ref "IC3") (pin "5") (pinfunction "VOUT_5") (pintype "bidirectional"))
      (node (ref "R25") (pin "1") (pinfunction "1_1") (pintype "passive"))
      (node (ref "U4") (pin "5") (pinfunction "VIN_5") (pintype "bidirectional"))
    )
    (net (code "6") (name "AP_WAKE_BT") (class "Default")
      (node (ref "IC4") (pin "3") (pinfunction "GPIO3_3") (pintype "bidirectional"))
      (node (ref "TP17") (pin "TP") (pinfunction "TP_TP") (pintype "input"))
    )
    (net (code "7") (name "BAT_M") (class "Default")
      (node (ref "C16") (pin "2") (pinfunction "2_2") (pintype "passive"))
      (node (ref "R6") (pin "2") (pinfunction "2_2") (pintype "passive"))
      (node (ref "U1") (pin "1") (pinfunction "S1_1") (pintype "output"))
      (node (ref "U1") (pin "2") (pinfunction "VSS_2") (pintype "power_in"))
    )
    (net (code "8") (name "BAT_MINUS") (class "Default")
      (node (ref "R6") (pin "1") (pinfunction "1_1") (pintype "passive"))
      (node (ref "R8") (pin "2") (pinfunction "2_2") (pintype "passive"))
      (node (ref "U1") (pin "6") (pinfunction "S2_6") (pintype "output"))
    )
    (net (code "9") (name "BAT_PLUS") (class "Default")
      (node (ref "C28") (pin "2") (pinfunction "2_2") (pintype "passive"))
      (node (ref "IC4") (pin "38") (pinfunction "BAT_38") (pintype "bidirectional"))
      (node (ref "IC4") (pin "39") (pinfunction "BAT_39") (pintype "bidirectional"))
      (node (ref "IC4") (pin "42") (pinfunction "BATSENSE_42") (pintype "bidirectional"))
      (node (ref "R15") (pin "1") (pinfunction "1_1") (pintype "passive"))
      (node (ref "R7") (pin "1") (pinfunction "1_1") (pintype "passive"))
      (node (ref "SV1") (pin "4") (pinfunction "4_4") (pintype "passive"))
    )
    (net (code "10") (name "BAT_TS") (class "Default")
      (node (ref "IC4") (pin "37") (pinfunction "TS_37") (pintype "bidirectional"))
      (node (ref "R24") (pin "1") (pinfunction "1_1") (pintype "passive"))
      (node (ref "TP26") (pin "TP") (pinfunction "TP_TP") (pintype "input"))
    )
    (net (code "11") (name "BUS_I2C_SCL") (class "Default")
      (node (ref "IC1") (pin "46") (pinfunction "PB7_46") (pintype "bidirectional"))
      (node (ref "IC4") (pin "2") (pinfunction "SCK_2") (pintype "bidirectional"))
      (node (ref "TP20") (pin "TP") (pinfunction "TP_TP") (pintype "input"))
      (node (ref "U40") (pin "C1") (pinfunction "SCL_C1") (pintype "bidirectional"))
    )
    (net (code "12") (name "BUS_I2C_SDA") (class "Default")
      (node (ref "IC1") (pin "45") (pinfunction "PB6_45") (pintype "bidirectional"))
      (node (ref "IC4") (pin "1") (pinfunction "SDA_1") (pintype "bidirectional"))
      (node (ref "TP21") (pin "TP") (pinfunction "TP_TP") (pintype "input"))
      (node (ref "U40") (pin "B1") (pinfunction "SDA_B1") (pintype "bidirectional"))
    )
    (net (code "13") (name "BUS_SPI_CLK") (class "Default")
      (node (ref "IC1") (pin "53") (pinfunction "PC1_53") (pintype "bidirectional"))
      (node (ref "IC2") (pin "6") (pinfunction "CLK_6") (pintype "bidirectional"))
    )
    (net (code "14") (name "BUS_SPI_CS") (class "Default")
      (node (ref "IC2") (pin "1") (pinfunction "/CS_1") (pintype "bidirectional"))
    )
    (net (code "15") (name "BUS_SPI_CS1") (class "Default")
      (node (ref "IC1") (pin "54") (pinfunction "PC2_54") (pintype "bidirectional"))
    )
    (net (code "16") (name "BUS_SPI_HOLD") (class "Default")
      (node (ref "IC2") (pin "7") (pinfunction "/HOLD_7") (pintype "bidirectional"))
    )
    (net (code "17") (name "BUS_SPI_MISO") (class "Default")
      (node (ref "IC1") (pin "52") (pinfunction "PC0_52") (pintype "bidirectional"))
      (node (ref "IC2") (pin "2") (pinfunction "DO_2") (pintype "bidirectional"))
    )
    (net (code "18") (name "BUS_SPI_MOSI") (class "Default")
      (node (ref "IC1") (pin "55") (pinfunction "PC3_55") (pintype "bidirectional"))
      (node (ref "IC2") (pin "5") (pinfunction "DI_5") (pintype "bidirectional"))
    )
    (net (code "19") (name "BUS_SPI_WP") (class "Default")
      (node (ref "IC2") (pin "3") (pinfunction "/WP_3") (pintype "bidirectional"))
    )
    (net (code "20") (name "BUS_UART0_RX") (class "Default")
      (node (ref "IC1") (pin "49") (pinfunction "PB9_49") (pintype "bidirectional"))
    )
    (net (code "21") (name "BUS_UART0_TX") (class "Default")
      (node (ref "IC1") (pin "48") (pinfunction "PB8_48") (pintype "bidirectional"))
    )
    (net (code "22") (name "BUS_VEXT") (class "Default")
      (node (ref "IC4") (pin "32") (pinfunction "ACIN_32") (pintype "bidirectional"))
      (node (ref "IC4") (pin "33") (pinfunction "ACIN_33") (pintype "bidirectional"))
      (node (ref "R19") (pin "1") (pinfunction "1_1") (pintype "passive"))
      (node (ref "SV1") (pin "3") (pinfunction "3_3") (pintype "passive"))
    )
    (net (code "23") (name "EXP") (class "Default")
      (node (ref "U1") (pin "7") (pinfunction "EXP_7") (pintype "power_in"))
    )
    (net (code "24") (name "EXTEN") (class "Default")
      (node (ref "IC4") (pin "20") (pinfunction "EXTEN_20") (pintype "bidirectional"))
      (node (ref "U10") (pin "3") (pinfunction "EN_3") (pintype "bidirectional"))
    )
    (net (code "25") (name "GND") (class "Default")
      (node (ref "C1") (pin "2") (pinfunction "2_2") (pintype "passive"))
      (node (ref "C10") (pin "2") (pinfunction "2_2") (pintype "passive"))
      (node (ref "C11") (pin "2") (pinfunction "2_2") (pintype "passive"))
      (node (ref "C12") (pin "2") (pinfunction "2_2") (pintype "passive"))
      (node (ref "C13") (pin "2") (pinfunction "2_2") (pintype "passive"))
      (node (ref "C14") (pin "2") (pinfunction "2_2") (pintype "passive"))
      (node (ref "C17") (pin "2") (pinfunction "2_2") (pintype "passive"))
      (node (ref "C18") (pin "2") (pinfunction "2_2") (pintype "passive"))
      (node (ref "C19") (pin "2") (pinfunction "2_2") (pintype "passive"))
      (node (ref "C2") (pin "2") (pinfunction "2_2") (pintype "passive"))
      (node (ref "C20") (pin "2") (pinfunction "2_2") (pintype "passive"))
      (node (ref "C21") (pin "2") (pinfunction "2_2") (pintype "passive"))
      (node (ref "C22") (pin "2") (pinfunction "2_2") (pintype "passive"))
      (node (ref "C23") (pin "2") (pinfunction "2_2") (pintype "passive"))
      (node (ref "C24") (pin "2") (pinfunction "2_2") (pintype "passive"))
      (node (ref "C25") (pin "2") (pinfunction "2_2") (pintype "passive"))
      (node (ref "C27") (pin "2") (pinfunction "2_2") (pintype "passive"))
      (node (ref "C28") (pin "1") (pinfunction "1_1") (pintype "passive"))
      (node (ref "C29") (pin "1") (pinfunction "1_1") (pintype "passive"))
      (node (ref "C3") (pin "2") (pinfunction "2_2") (pintype "passive"))
      (node (ref "C30") (pin "2") (pinfunction "2_2") (pintype "passive"))
      (node (ref "C31") (pin "1") (pinfunction "1_1") (pintype "passive"))
      (node (ref "C32") (pin "1") (pinfunction "1_1") (pintype "passive"))
      (node (ref "C33") (pin "1") (pinfunction "1_1") (pintype "passive"))
      (node (ref "C34") (pin "1") (pinfunction "1_1") (pintype "passive"))
      (node (ref "C35") (pin "1") (pinfunction "1_1") (pintype "passive"))
      (node (ref "C36") (pin "1") (pinfunction "1_1") (pintype "passive"))
      (node (ref "C37") (pin "1") (pinfunction "1_1") (pintype "passive"))
      (node (ref "C38") (pin "1") (pinfunction "1_1") (pintype "passive"))
      (node (ref "C39") (pin "1") (pinfunction "1_1") (pintype "passive"))
      (node (ref "C4") (pin "2") (pinfunction "2_2") (pintype "passive"))
      (node (ref "C40") (pin "2") (pinfunction "2_2") (pintype "passive"))
      (node (ref "C42") (pin "2") (pinfunction "2_2") (pintype "passive"))
      (node (ref "C43") (pin "2") (pinfunction "2_2") (pintype "passive"))
      (node (ref "C44") (pin "2") (pinfunction "2_2") (pintype "passive"))
      (node (ref "C46") (pin "1") (pinfunction "1_1") (pintype "passive"))
      (node (ref "C47") (pin "1") (pinfunction "1_1") (pintype "passive"))
      (node (ref "C48") (pin "1") (pinfunction "1_1") (pintype "passive"))
      (node (ref "C49") (pin "1") (pinfunction "1_1") (pintype "passive"))
      (node (ref "C5") (pin "2") (pinfunction "2_2") (pintype "passive"))
      (node (ref "C50") (pin "1") (pinfunction "1_1") (pintype "passive"))
      (node (ref "C51") (pin "2") (pinfunction "2_2") (pintype "passive"))
      (node (ref "C52") (pin "2") (pinfunction "2_2") (pintype "passive"))
      (node (ref "C53") (pin "2") (pinfunction "2_2") (pintype "passive"))
      (node (ref "C54") (pin "2") (pinfunction "2_2") (pintype "passive"))
      (node (ref "C55") (pin "2") (pinfunction "2_2") (pintype "passive"))
      (node (ref "C56") (pin "2") (pinfunction "2_2") (pintype "passive"))
      (node (ref "C57") (pin "2") (pinfunction "2_2") (pintype "passive"))
      (node (ref "C6") (pin "2") (pinfunction "2_2") (pintype "passive"))
      (node (ref "C7") (pin "2") (pinfunction "2_2") (pintype "passive"))
      (node (ref "C8") (pin "2") (pinfunction "2_2") (pintype "passive"))
      (node (ref "C9") (pin "2") (pinfunction "2_2") (pintype "passive"))
      (node (ref "CON1") (pin "GND1") (pinfunction "GND_GND1") (pintype "power_in"))
      (node (ref "CON1") (pin "GND2") (pinfunction "GND_GND2") (pintype "power_in"))
      (node (ref "CON1") (pin "GND3") (pinfunction "GND_GND3") (pintype "power_in"))
      (node (ref "CON1") (pin "GND4") (pinfunction "GND_GND4") (pintype "power_in"))
      (node (ref "CON1") (pin "P$6") (pinfunction "VSS_P$6") (pintype "bidirectional"))
      (node (ref "CON2") (pin "5") (pinfunction "GND_5") (pintype "bidirectional"))
      (node (ref "CON2") (pin "SH1") (pinfunction "GND_SH1") (pintype "bidirectional"))
      (node (ref "CON2") (pin "SH2") (pinfunction "GND_SH2") (pintype "bidirectional"))
      (node (ref "CON2") (pin "SH3") (pinfunction "GND_SH3") (pintype "bidirectional"))
      (node (ref "CON2") (pin "SH4") (pinfunction "GND_SH4") (pintype "bidirectional"))
      (node (ref "CON2") (pin "SH5") (pinfunction "GND_SH5") (pintype "bidirectional"))
      (node (ref "CON2") (pin "SH6") (pinfunction "GND_SH6") (pintype "bidirectional"))
      (node (ref "CON2") (pin "SH7") (pinfunction "GND_SH7") (pintype "bidirectional"))
      (node (ref "CON2") (pin "SH8") (pinfunction "GND_SH8") (pintype "bidirectional"))
      (node (ref "D1") (pin "2") (pinfunction "C_2") (pintype "passive"))
      (node (ref "D10") (pin "2") (pinfunction "C_2") (pintype "passive"))
      (node (ref "D11") (pin "2") (pinfunction "C_2") (pintype "passive"))
      (node (ref "D12") (pin "2") (pinfunction "C_2") (pintype "passive"))
      (node (ref "D2") (pin "2") (pinfunction "C_2") (pintype "passive"))
      (node (ref "D3") (pin "2") (pinfunction "C_2") (pintype "passive"))
      (node (ref "D4") (pin "2") (pinfunction "C_2") (pintype "passive"))
      (node (ref "D5") (pin "2") (pinfunction "C_2") (pintype "passive"))
      (node (ref "D6") (pin "2") (pinfunction "C_2") (pintype "passive"))
      (node (ref "D7") (pin "2") (pinfunction "C_2") (pintype "passive"))
      (node (ref "D8") (pin "1") (pinfunction "A_1") (pintype "passive"))
      (node (ref "D9") (pin "2") (pinfunction "C_2") (pintype "passive"))
      (node (ref "IC1") (pin "116") (pinfunction "AGND_116") (pintype "bidirectional"))
      (node (ref "IC1") (pin "P$2") (pinfunction "GND_P$2") (pintype "bidirectional"))
      (node (ref "IC2") (pin "4") (pinfunction "GND_4") (pintype "bidirectional"))
      (node (ref "IC3") (pin "2") (pinfunction "GND_2") (pintype "bidirectional"))
      (node (ref "IC4") (pin "16") (pinfunction "PGND3_16") (pintype "bidirectional"))
      (node (ref "IC4") (pin "22") (pinfunction "AGND_22") (pintype "bidirectional"))
      (node (ref "IC4") (pin "46") (pinfunction "PGND1_46") (pintype "bidirectional"))
      (node (ref "IC4") (pin "49") (pinfunction "EP_49") (pintype "bidirectional"))
      (node (ref "IC4") (pin "9") (pinfunction "PGND2_9") (pintype "bidirectional"))
      (node (ref "IC4") (pin "P$1") (pinfunction "EP_P$1") (pintype "bidirectional"))
      (node (ref "IC4") (pin "P$2") (pinfunction "EP_P$2") (pintype "bidirectional"))
      (node (ref "IC4") (pin "P$3") (pinfunction "EP_P$3") (pintype "bidirectional"))
      (node (ref "IC4") (pin "P$4") (pinfunction "EP_P$4") (pintype "bidirectional"))
      (node (ref "IC4") (pin "P$5") (pinfunction "EP_P$5") (pintype "bidirectional"))
      (node (ref "IC4") (pin "P$6") (pinfunction "EP_P$6") (pintype "bidirectional"))
      (node (ref "IC4") (pin "P$7") (pinfunction "EP_P$7") (pintype "bidirectional"))
      (node (ref "IC4") (pin "P$8") (pinfunction "EP_P$8") (pintype "bidirectional"))
      (node (ref "IC4") (pin "P$9") (pinfunction "EP_P$9") (pintype "bidirectional"))
      (node (ref "J1") (pin "1") (pinfunction "GND_1") (pintype "passive"))
      (node (ref "J1") (pin "2") (pinfunction "GND_2") (pintype "passive"))
      (node (ref "R16") (pin "2") (pinfunction "2_2") (pintype "passive"))
      (node (ref "R17") (pin "2") (pinfunction "2_2") (pintype "passive"))
      (node (ref "R2") (pin "1") (pinfunction "1_1") (pintype "passive"))
      (node (ref "R22") (pin "1") (pinfunction "1_1") (pintype "passive"))
      (node (ref "R24") (pin "2") (pinfunction "2_2") (pintype "passive"))
      (node (ref "R26") (pin "2") (pinfunction "2_2") (pintype "passive"))
      (node (ref "R3") (pin "1") (pinfunction "1_1") (pintype "passive"))
      (node (ref "R5") (pin "2") (pinfunction "2_2") (pintype "passive"))
      (node (ref "SV1") (pin "1") (pinfunction "1_1") (pintype "passive"))
      (node (ref "U10") (pin "2") (pinfunction "GND_2") (pintype "bidirectional"))
      (node (ref "U3") (pin "1") (pinfunction "GND_1") (pintype "bidirectional"))
      (node (ref "U3") (pin "20") (pinfunction "GND_20") (pintype "bidirectional"))
      (node (ref "U3") (pin "3") (pinfunction "GND_3") (pintype "bidirectional"))
      (node (ref "U3") (pin "31") (pinfunction "GND_31") (pintype "bidirectional"))
      (node (ref "U3") (pin "33") (pinfunction "GND_33") (pintype "bidirectional"))
      (node (ref "U3") (pin "36") (pinfunction "GND_36") (pintype "bidirectional"))
      (node (ref "U4") (pin "2") (pinfunction "GND_2") (pintype "bidirectional"))
      (node (ref "U40") (pin "D1") (pinfunction "GND_D1") (pintype "bidirectional"))
    )
    (net (code "26") (name "GPIO2") (class "Default")
      (node (ref "IC4") (pin "5") (pinfunction "GPIO2_5") (pintype "bidirectional"))
      (node (ref "TP18") (pin "TP") (pinfunction "TP_TP") (pintype "input"))
    )
    (net (code "27") (name "IPS") (class "Default")
      (node (ref "C14") (pin "1") (pinfunction "1_1") (pintype "passive"))
      (node (ref "C29") (pin "2") (pinfunction "2_2") (pintype "passive"))
      (node (ref "C30") (pin "1") (pinfunction "1_1") (pintype "passive"))
      (node (ref "C32") (pin "2") (pinfunction "2_2") (pintype "passive"))
      (node (ref "C34") (pin "2") (pinfunction "2_2") (pintype "passive"))
      (node (ref "C36") (pin "2") (pinfunction "2_2") (pintype "passive"))
      (node (ref "C50") (pin "2") (pinfunction "2_2") (pintype "passive"))
      (node (ref "C56") (pin "1") (pinfunction "1_1") (pintype "passive"))
      (node (ref "IC3") (pin "6") (pinfunction "VIN_6") (pintype "bidirectional"))
      (node (ref "IC4") (pin "14") (pinfunction "VIN3_14") (pintype "bidirectional"))
      (node (ref "IC4") (pin "21") (pinfunction "APS_21") (pintype "bidirectional"))
      (node (ref "IC4") (pin "29") (pinfunction "DC3SET_29") (pintype "bidirectional"))
      (node (ref "IC4") (pin "34") (pinfunction "IPSOUT_34") (pintype "bidirectional"))
      (node (ref "IC4") (pin "35") (pinfunction "IPSOUT_35") (pintype "bidirectional"))
      (node (ref "IC4") (pin "40") (pinfunction "LDO3IN_40") (pintype "bidirectional"))
      (node (ref "IC4") (pin "44") (pinfunction "VIN1_44") (pintype "bidirectional"))
      (node (ref "IC4") (pin "7") (pinfunction "VIN2_7") (pintype "bidirectional"))
      (node (ref "L5") (pin "1") (pinfunction "1_1") (pintype "passive"))
      (node (ref "U10") (pin "1") (pinfunction "VIN_1") (pintype "bidirectional"))
    )
    (net (code "28") (name "LDO2") (class "Default")
      (node (ref "C37") (pin "2") (pinfunction "2_2") (pintype "passive"))
      (node (ref "IC4") (pin "12") (pinfunction "LDO2_12") (pintype "bidirectional"))
      (node (ref "TP24") (pin "TP") (pinfunction "TP_TP") (pintype "input"))
    )
    (net (code "29") (name "LDO3") (class "Default")
      (node (ref "C51") (pin "1") (pinfunction "1_1") (pintype "passive"))
      (node (ref "IC4") (pin "41") (pinfunction "LDO3_41") (pintype "bidirectional"))
      (node (ref "TP25") (pin "TP") (pinfunction "TP_TP") (pintype "input"))
    )
    (net (code "30") (name "LDO4") (class "Default")
      (node (ref "C38") (pin "2") (pinfunction "2_2") (pintype "passive"))
      (node (ref "IC4") (pin "11") (pinfunction "LDO4_11") (pintype "bidirectional"))
      (node (ref "TP23") (pin "TP") (pinfunction "TP_TP") (pintype "input"))
    )
    (net (code "31") (name "LED_BLUE") (class "Default")
      (node (ref "LED1") (pin "1") (pinfunction "1_1") (pintype "passive"))
      (node (ref "U40") (pin "D2") (pinfunction "OUT3_D2") (pintype "bidirectional"))
    )
    (net (code "32") (name "LED_ENABLE") (class "Default")
      (node (ref "U40") (pin "A1") (pinfunction "SDB_A1") (pintype "bidirectional"))
    )
    (net (code "33") (name "LED_GREEN") (class "Default")
      (node (ref "LED1") (pin "4") (pinfunction "4_4") (pintype "passive"))
      (node (ref "U40") (pin "C2") (pinfunction "OUT2_C2") (pintype "bidirectional"))
    )
    (net (code "34") (name "LED_RED") (class "Default")
      (node (ref "LED1") (pin "3") (pinfunction "3_3") (pintype "passive"))
      (node (ref "U40") (pin "B2") (pinfunction "OUT1_B2") (pintype "bidirectional"))
    )
    (net (code "35") (name "N$2") (class "Default")
      (node (ref "C24") (pin "1") (pinfunction "1_1") (pintype "passive"))
      (node (ref "CON1") (pin "P$4") (pinfunction "VDD_P$4") (pintype "input"))
      (node (ref "D8") (pin "2") (pinfunction "C_2") (pintype "passive"))
    )
    (net (code "36") (name "Net-(C45-Pad1)") (class "Default")
      (node (ref "C45") (pin "1") (pinfunction "1_1") (pintype "passive"))
      (node (ref "C46") (pin "2") (pinfunction "2_2") (pintype "passive"))
      (node (ref "R18") (pin "2") (pinfunction "2_2") (pintype "passive"))
    )
    (net (code "37") (name "Net-(C48-Pad2)") (class "Default")
      (node (ref "C48") (pin "2") (pinfunction "2_2") (pintype "passive"))
      (node (ref "R19") (pin "2") (pinfunction "2_2") (pintype "passive"))
    )
    (net (code "38") (name "Net-(CON2-VCC)") (class "Default")
      (node (ref "CON2") (pin "1") (pinfunction "VCC_1") (pintype "bidirectional"))
      (node (ref "F1") (pin "2") (pinfunction "2_2") (pintype "passive"))
    )
    (net (code "39") (name "Net-(IC1B-MCSI-CKN)") (class "Default")
      (node (ref "IC1") (pin "87") (pinfunction "MCSI-CKN_87") (pintype "bidirectional"))
      (node (ref "TP27") (pin "TP") (pinfunction "TP_TP") (pintype "input"))
    )
    (net (code "40") (name "Net-(IC1B-MCSI-CKP)") (class "Default")
      (node (ref "IC1") (pin "86") (pinfunction "MCSI-CKP_86") (pintype "bidirectional"))
      (node (ref "TP30") (pin "TP") (pinfunction "TP_TP") (pintype "input"))
    )
    (net (code "41") (name "Net-(IC1B-MCSI-D0N)") (class "Default")
      (node (ref "IC1") (pin "82") (pinfunction "MCSI-D0N_82") (pintype "bidirectional"))
      (node (ref "TP33") (pin "TP") (pinfunction "TP_TP") (pintype "input"))
    )
    (net (code "42") (name "Net-(IC1B-MCSI-D0P)") (class "Default")
      (node (ref "IC1") (pin "81") (pinfunction "MCSI-D0P_81") (pintype "bidirectional"))
      (node (ref "TP34") (pin "TP") (pinfunction "TP_TP") (pintype "input"))
    )
    (net (code "43") (name "Net-(IC1B-MCSI-D1N)") (class "Default")
      (node (ref "IC1") (pin "84") (pinfunction "MCSI-D1N_84") (pintype "bidirectional"))
      (node (ref "TP31") (pin "TP") (pinfunction "TP_TP") (pintype "input"))
    )
    (net (code "44") (name "Net-(IC1B-MCSI-D1P)") (class "Default")
      (node (ref "IC1") (pin "83") (pinfunction "MCSI-D1P_83") (pintype "bidirectional"))
      (node (ref "TP32") (pin "TP") (pinfunction "TP_TP") (pintype "input"))
    )
    (net (code "45") (name "Net-(IC1L-EPHY_LINK)") (class "Default")
      (node (ref "IC1") (pin "77") (pinfunction "EPHY_LINK_77") (pintype "bidirectional"))
      (node (ref "TP10") (pin "TP") (pinfunction "TP_TP") (pintype "input"))
    )
    (net (code "46") (name "Net-(IC1L-EPHY_RTX)") (class "Default")
      (node (ref "IC1") (pin "94") (pinfunction "EPHY_RTX_94") (pintype "bidirectional"))
      (node (ref "TP8") (pin "TP") (pinfunction "TP_TP") (pintype "input"))
    )
    (net (code "47") (name "Net-(IC1L-EPHY_RXN)") (class "Default")
      (node (ref "IC1") (pin "89") (pinfunction "EPHY_RXN_89") (pintype "bidirectional"))
      (node (ref "TP4") (pin "TP") (pinfunction "TP_TP") (pintype "input"))
    )
    (net (code "48") (name "Net-(IC1L-EPHY_RXP)") (class "Default")
      (node (ref "IC1") (pin "90") (pinfunction "EPHY_RXP_90") (pintype "bidirectional"))
      (node (ref "TP5") (pin "TP") (pinfunction "TP_TP") (pintype "input"))
    )
    (net (code "49") (name "Net-(IC1L-EPHY_SPD)") (class "Default")
      (node (ref "IC1") (pin "78") (pinfunction "EPHY_SPD_78") (pintype "bidirectional"))
      (node (ref "TP9") (pin "TP") (pinfunction "TP_TP") (pintype "input"))
    )
    (net (code "50") (name "Net-(IC1L-EPHY_TXN)") (class "Default")
      (node (ref "IC1") (pin "91") (pinfunction "EPHY_TXN_91") (pintype "bidirectional"))
      (node (ref "TP6") (pin "TP") (pinfunction "TP_TP") (pintype "input"))
    )
    (net (code "51") (name "Net-(IC1L-EPHY_TXP)") (class "Default")
      (node (ref "IC1") (pin "92") (pinfunction "EPHY_TXP_92") (pintype "bidirectional"))
      (node (ref "TP7") (pin "TP") (pinfunction "TP_TP") (pintype "input"))
    )
    (net (code "52") (name "Net-(IC3-SW)") (class "Default")
      (node (ref "IC3") (pin "1") (pinfunction "SW_1") (pintype "bidirectional"))
      (node (ref "L5") (pin "2") (pinfunction "2_2") (pintype "passive"))
    )
    (net (code "53") (name "Net-(IC3-VFB)") (class "Default")
      (node (ref "IC3") (pin "4") (pinfunction "VFB_4") (pintype "bidirectional"))
      (node (ref "R25") (pin "2") (pinfunction "2_2") (pintype "passive"))
      (node (ref "R26") (pin "1") (pinfunction "1_1") (pintype "passive"))
    )
    (net (code "54") (name "Net-(IC4-CHSENSE)") (class "Default")
      (node (ref "C31") (pin "2") (pinfunction "2_2") (pintype "passive"))
      (node (ref "IC4") (pin "43") (pinfunction "CHSENSE_43") (pintype "bidirectional"))
      (node (ref "L1") (pin "2") (pinfunction "2_2") (pintype "passive"))
      (node (ref "R15") (pin "2") (pinfunction "2_2") (pintype "passive"))
    )
    (net (code "55") (name "Net-(IC4-GPIO0)") (class "Default")
      (node (ref "IC4") (pin "19") (pinfunction "GPIO0_19") (pintype "bidirectional"))
      (node (ref "TP29") (pin "TP") (pinfunction "TP_TP") (pintype "input"))
    )
    (net (code "56") (name "Net-(IC4-GPIO1)") (class "Default")
      (node (ref "IC4") (pin "18") (pinfunction "GPIO1_18") (pintype "bidirectional"))
      (node (ref "TP28") (pin "TP") (pinfunction "TP_TP") (pintype "input"))
    )
    (net (code "57") (name "Net-(IC4-IRQ)") (class "Default")
      (node (ref "IC4") (pin "48") (pinfunction "IRQ_48") (pintype "bidirectional"))
      (node (ref "TP19") (pin "TP") (pinfunction "TP_TP") (pintype "input"))
    )
    (net (code "58") (name "Net-(IC4-LX1)") (class "Default")
      (node (ref "IC4") (pin "45") (pinfunction "LX1_45") (pintype "bidirectional"))
      (node (ref "L1") (pin "1") (pinfunction "1_1") (pintype "passive"))
    )
    (net (code "59") (name "Net-(IC4-LX2)") (class "Default")
      (node (ref "IC4") (pin "8") (pinfunction "LX2_8") (pintype "bidirectional"))
      (node (ref "L2") (pin "1") (pinfunction "1_1") (pintype "passive"))
    )
    (net (code "60") (name "Net-(IC4-LX3)") (class "Default")
      (node (ref "IC4") (pin "15") (pinfunction "LX3_15") (pintype "bidirectional"))
      (node (ref "L3") (pin "1") (pinfunction "1_1") (pintype "passive"))
    )
    (net (code "61") (name "Net-(IC4-~{OE})") (class "Default")
      (node (ref "IC4") (pin "4") (pinfunction "~{OE}_4") (pintype "bidirectional"))
      (node (ref "R22") (pin "2") (pinfunction "2_2") (pintype "passive"))
    )
    (net (code "62") (name "Net-(J1-SIG)") (class "Default")
      (node (ref "C47") (pin "2") (pinfunction "2_2") (pintype "passive"))
      (node (ref "J1") (pin "3") (pinfunction "SIG_3") (pintype "passive"))
      (node (ref "R18") (pin "1") (pinfunction "1_1") (pintype "passive"))
    )
    (net (code "63") (name "Net-(R10-Pad2)") (class "Default")
      (node (ref "R10") (pin "2") (pinfunction "2_2") (pintype "passive"))
      (node (ref "R11") (pin "2") (pinfunction "2_2") (pintype "passive"))
      (node (ref "R12") (pin "2") (pinfunction "2_2") (pintype "passive"))
      (node (ref "R13") (pin "2") (pinfunction "2_2") (pintype "passive"))
      (node (ref "R14") (pin "2") (pinfunction "2_2") (pintype "passive"))
      (node (ref "R9") (pin "2") (pinfunction "2_2") (pintype "passive"))
    )
    (net (code "64") (name "Net-(U1-VDD)") (class "Default")
      (node (ref "C16") (pin "1") (pinfunction "1_1") (pintype "passive"))
      (node (ref "R7") (pin "2") (pinfunction "2_2") (pintype "passive"))
      (node (ref "U1") (pin "3") (pinfunction "VDD_3") (pintype "power_in"))
    )
    (net (code "65") (name "Net-(U1-VM)") (class "Default")
      (node (ref "R8") (pin "1") (pinfunction "1_1") (pintype "passive"))
      (node (ref "U1") (pin "5") (pinfunction "VM_5") (pintype "input"))
    )
    (net (code "66") (name "Net-(U3-WL_BT_ANT)") (class "Default")
      (node (ref "C45") (pin "2") (pinfunction "2_2") (pintype "passive"))
      (node (ref "U3") (pin "2") (pinfunction "WL_BT_ANT_2") (pintype "bidirectional"))
    )
    (net (code "67") (name "Net-(U10-FB)") (class "Default")
      (node (ref "C15") (pin "2") (pinfunction "2_2") (pintype "passive"))
      (node (ref "R4") (pin "1") (pinfunction "1_1") (pintype "passive"))
      (node (ref "R5") (pin "1") (pinfunction "1_1") (pintype "passive"))
      (node (ref "U10") (pin "4") (pinfunction "FB_4") (pintype "bidirectional"))
    )
    (net (code "68") (name "Net-(U10-LX)") (class "Default")
      (node (ref "L4") (pin "1") (pinfunction "1_1") (pintype "passive"))
      (node (ref "U10") (pin "5") (pinfunction "LX_5") (pintype "bidirectional"))
    )
    (net (code "69") (name "PWR_ON") (class "Default")
      (node (ref "IC4") (pin "47") (pinfunction "PWRON_47") (pintype "bidirectional"))
      (node (ref "TP22") (pin "TP") (pinfunction "TP_TP") (pintype "input"))
    )
    (net (code "70") (name "RCC_HSE_IN") (class "Default")
      (node (ref "C3") (pin "1") (pinfunction "1_1") (pintype "passive"))
      (node (ref "IC1") (pin "75") (pinfunction "X24IN_75") (pintype "bidirectional"))
      (node (ref "Q1") (pin "3") (pinfunction "2_3") (pintype "passive"))
    )
    (net (code "71") (name "RCC_HSE_OUT") (class "Default")
      (node (ref "C4") (pin "1") (pinfunction "1_1") (pintype "passive"))
      (node (ref "IC1") (pin "74") (pinfunction "X24OUT_74") (pintype "bidirectional"))
      (node (ref "Q1") (pin "1") (pinfunction "1_1") (pintype "passive"))
    )
    (net (code "72") (name "RCC_LSE_IN") (class "Default")
      (node (ref "C5") (pin "1") (pinfunction "1_1") (pintype "passive"))
      (node (ref "IC1") (pin "96") (pinfunction "X32IN_96") (pintype "bidirectional"))
      (node (ref "Q2") (pin "2") (pinfunction "2_2") (pintype "passive"))
    )
    (net (code "73") (name "RCC_LSE_OUT") (class "Default")
      (node (ref "C6") (pin "1") (pinfunction "1_1") (pintype "passive"))
      (node (ref "IC1") (pin "95") (pinfunction "X32OUT_95") (pintype "bidirectional"))
      (node (ref "Q2") (pin "1") (pinfunction "1_1") (pintype "passive"))
    )
    (net (code "74") (name "SDC0_CLK") (class "Default")
      (node (ref "CON1") (pin "P$5") (pinfunction "CLK_P$5") (pintype "bidirectional"))
      (node (ref "D4") (pin "1") (pinfunction "A_1") (pintype "passive"))
      (node (ref "IC1") (pin "105") (pinfunction "PF2_105") (pintype "bidirectional"))
    )
    (net (code "75") (name "SDC0_CMD") (class "Default")
      (node (ref "CON1") (pin "P$3") (pinfunction "CMD_P$3") (pintype "input"))
      (node (ref "D3") (pin "1") (pinfunction "A_1") (pintype "passive"))
      (node (ref "IC1") (pin "103") (pinfunction "PF3_103") (pintype "bidirectional"))
      (node (ref "R11") (pin "1") (pinfunction "1_1") (pintype "passive"))
    )
    (net (code "76") (name "SDC0_D0") (class "Default")
      (node (ref "CON1") (pin "P$7") (pinfunction "DAT0_P$7") (pintype "power_in"))
      (node (ref "D5") (pin "1") (pinfunction "A_1") (pintype "passive"))
      (node (ref "IC1") (pin "106") (pinfunction "PF1_106") (pintype "bidirectional"))
      (node (ref "R9") (pin "1") (pinfunction "1_1") (pintype "passive"))
    )
    (net (code "77") (name "SDC0_D1") (class "Default")
      (node (ref "CON1") (pin "P$8") (pinfunction "DAT1_P$8") (pintype "power_in"))
      (node (ref "D6") (pin "1") (pinfunction "A_1") (pintype "passive"))
      (node (ref "IC1") (pin "107") (pinfunction "PF0_107") (pintype "bidirectional"))
      (node (ref "R10") (pin "1") (pinfunction "1_1") (pintype "passive"))
    )
    (net (code "78") (name "SDC0_D2") (class "Default")
      (node (ref "CON1") (pin "P$1") (pinfunction "DAT2_P$1") (pintype "output"))
      (node (ref "D1") (pin "1") (pinfunction "A_1") (pintype "passive"))
      (node (ref "IC1") (pin "101") (pinfunction "PF5_101") (pintype "bidirectional"))
      (node (ref "R13") (pin "1") (pinfunction "1_1") (pintype "passive"))
    )
    (net (code "79") (name "SDC0_D3") (class "Default")
      (node (ref "CON1") (pin "P$2") (pinfunction "CD/DAT3_P$2") (pintype "input"))
      (node (ref "D2") (pin "1") (pinfunction "A_1") (pintype "passive"))
      (node (ref "IC1") (pin "102") (pinfunction "PF4_102") (pintype "bidirectional"))
      (node (ref "R12") (pin "1") (pinfunction "1_1") (pintype "passive"))
    )
    (net (code "80") (name "SDC0_DET") (class "Default")
      (node (ref "CON1") (pin "P$13") (pinfunction "CD_P$13") (pintype "power_in"))
      (node (ref "D7") (pin "1") (pinfunction "A_1") (pintype "passive"))
      (node (ref "IC1") (pin "100") (pinfunction "PF6_100") (pintype "bidirectional"))
      (node (ref "R14") (pin "1") (pinfunction "1_1") (pintype "passive"))
    )
    (net (code "81") (name "SDC1_CLK") (class "Default")
      (node (ref "IC1") (pin "5") (pinfunction "PG0_5") (pintype "bidirectional"))
      (node (ref "TP11") (pin "TP") (pinfunction "TP_TP") (pintype "input"))
      (node (ref "U3") (pin "17") (pinfunction "SDIO_CLK_17") (pintype "bidirectional"))
    )
    (net (code "82") (name "SDC1_CMD") (class "Default")
      (node (ref "IC1") (pin "4") (pinfunction "PG1_4") (pintype "bidirectional"))
      (node (ref "TP12") (pin "TP") (pinfunction "TP_TP") (pintype "input"))
      (node (ref "U3") (pin "16") (pinfunction "SDIO_CMD_16") (pintype "bidirectional"))
    )
    (net (code "83") (name "SDC1_D0") (class "Default")
      (node (ref "IC1") (pin "3") (pinfunction "PG2_3") (pintype "bidirectional"))
      (node (ref "TP13") (pin "TP") (pinfunction "TP_TP") (pintype "input"))
      (node (ref "U3") (pin "18") (pinfunction "SDIO_D0_18") (pintype "bidirectional"))
    )
    (net (code "84") (name "SDC1_D1") (class "Default")
      (node (ref "IC1") (pin "2") (pinfunction "PG3_2") (pintype "bidirectional"))
      (node (ref "TP14") (pin "TP") (pinfunction "TP_TP") (pintype "input"))
      (node (ref "U3") (pin "19") (pinfunction "SDIO_D1_19") (pintype "bidirectional"))
    )
    (net (code "85") (name "SDC1_D2") (class "Default")
      (node (ref "IC1") (pin "1") (pinfunction "PG4_1") (pintype "bidirectional"))
      (node (ref "TP15") (pin "TP") (pinfunction "TP_TP") (pintype "input"))
      (node (ref "U3") (pin "14") (pinfunction "SDIO_D2_14") (pintype "bidirectional"))
    )
    (net (code "86") (name "SDC1_D3") (class "Default")
      (node (ref "IC1") (pin "128") (pinfunction "PG5_128") (pintype "bidirectional"))
      (node (ref "TP16") (pin "TP") (pinfunction "TP_TP") (pintype "input"))
      (node (ref "U3") (pin "15") (pinfunction "SDIO_D3_15") (pintype "bidirectional"))
    )
    (net (code "87") (name "SVREF") (class "Default")
      (node (ref "C26") (pin "1") (pinfunction "1_1") (pintype "passive"))
      (node (ref "C27") (pin "1") (pinfunction "1_1") (pintype "passive"))
      (node (ref "IC1") (pin "63") (pinfunction "SVREF1_63") (pintype "bidirectional"))
      (node (ref "IC1") (pin "71") (pinfunction "SVREF0_71") (pintype "bidirectional"))
      (node (ref "R1") (pin "2") (pinfunction "2_2") (pintype "passive"))
      (node (ref "R2") (pin "2") (pinfunction "2_2") (pintype "passive"))
    )
    (net (code "88") (name "SZQ") (class "Default")
      (node (ref "IC1") (pin "73") (pinfunction "SZQ_73") (pintype "bidirectional"))
      (node (ref "R3") (pin "2") (pinfunction "2_2") (pintype "passive"))
    )
    (net (code "89") (name "USB_ID") (class "Default")
      (node (ref "IC4") (pin "6") (pinfunction "~{VBUSEN}_6") (pintype "bidirectional"))
      (node (ref "R16") (pin "1") (pinfunction "1_1") (pintype "passive"))
      (node (ref "R21") (pin "2") (pinfunction "2_2") (pintype "passive"))
      (node (ref "U4") (pin "4") (pinfunction "EN_4") (pintype "bidirectional"))
    )
    (net (code "90") (name "USB_OTG_D_N") (class "Default")
      (node (ref "CON2") (pin "2") (pinfunction "DM_2") (pintype "bidirectional"))
      (node (ref "D10") (pin "1") (pinfunction "A_1") (pintype "passive"))
      (node (ref "IC1") (pin "110") (pinfunction "USB_DM_110") (pintype "bidirectional"))
    )
    (net (code "91") (name "USB_OTG_D_P") (class "Default")
      (node (ref "CON2") (pin "3") (pinfunction "DP_3") (pintype "bidirectional"))
      (node (ref "D11") (pin "1") (pinfunction "A_1") (pintype "passive"))
      (node (ref "IC1") (pin "111") (pinfunction "USB_DP_111") (pintype "bidirectional"))
    )
    (net (code "92") (name "USB_OTG_ID") (class "Default")
      (node (ref "CON2") (pin "4") (pinfunction "ID_4") (pintype "bidirectional"))
      (node (ref "D12") (pin "1") (pinfunction "A_1") (pintype "passive"))
      (node (ref "R20") (pin "1") (pinfunction "1_1") (pintype "passive"))
      (node (ref "R21") (pin "1") (pinfunction "1_1") (pintype "passive"))
    )
    (net (code "93") (name "USB_VBUS") (class "Default")
      (node (ref "C49") (pin "2") (pinfunction "2_2") (pintype "passive"))
      (node (ref "C53") (pin "1") (pinfunction "1_1") (pintype "passive"))
      (node (ref "C54") (pin "1") (pinfunction "1_1") (pintype "passive"))
      (node (ref "D9") (pin "1") (pinfunction "A_1") (pintype "passive"))
      (node (ref "F1") (pin "1") (pinfunction "1_1") (pintype "passive"))
      (node (ref "IC4") (pin "31") (pinfunction "VBUS_31") (pintype "bidirectional"))
      (node (ref "U4") (pin "1") (pinfunction "VOUT_1") (pintype "bidirectional"))
    )
    (net (code "94") (name "VBIAS") (class "Default")
      (node (ref "IC4") (pin "23") (pinfunction "BIAS_23") (pintype "bidirectional"))
      (node (ref "R17") (pin "1") (pinfunction "1_1") (pintype "passive"))
    )
    (net (code "95") (name "VCC_RTC") (class "Default")
      (node (ref "C44") (pin "1") (pinfunction "1_1") (pintype "passive"))
      (node (ref "IC4") (pin "28") (pinfunction "LDO1_28") (pintype "bidirectional"))
      (node (ref "R23") (pin "2") (pinfunction "2_2") (pintype "passive"))
      (node (ref "TP3") (pin "TP") (pinfunction "TP_TP") (pintype "input"))
    )
    (net (code "96") (name "VDD_CPU") (class "Default")
      (node (ref "C10") (pin "1") (pinfunction "1_1") (pintype "passive"))
      (node (ref "C11") (pin "1") (pinfunction "1_1") (pintype "passive"))
      (node (ref "C12") (pin "1") (pinfunction "1_1") (pintype "passive"))
      (node (ref "C7") (pin "1") (pinfunction "1_1") (pintype "passive"))
      (node (ref "C8") (pin "1") (pinfunction "1_1") (pintype "passive"))
      (node (ref "C9") (pin "1") (pinfunction "1_1") (pintype "passive"))
      (node (ref "IC1") (pin "20") (pinfunction "VDD-CPU3_20") (pintype "bidirectional"))
      (node (ref "IC1") (pin "21") (pinfunction "VDD-CPU2_21") (pintype "bidirectional"))
      (node (ref "IC1") (pin "25") (pinfunction "VDD-CPU1_25") (pintype "bidirectional"))
      (node (ref "IC1") (pin "26") (pinfunction "VDD-CPU0_26") (pintype "bidirectional"))
      (node (ref "IC1") (pin "38") (pinfunction "VDD-CPU4_38") (pintype "bidirectional"))
      (node (ref "IC1") (pin "47") (pinfunction "VDD-CPU5_47") (pintype "bidirectional"))
      (node (ref "IC1") (pin "51") (pinfunction "VDD-CPU6_51") (pintype "bidirectional"))
      (node (ref "IC1") (pin "56") (pinfunction "VDD-CPU7_56") (pintype "bidirectional"))
    )
    (net (code "97") (name "VDD_SYS") (class "Default")
      (node (ref "C1") (pin "1") (pinfunction "1_1") (pintype "passive"))
      (node (ref "C13") (pin "1") (pinfunction "1_1") (pintype "passive"))
      (node (ref "C17") (pin "1") (pinfunction "1_1") (pintype "passive"))
      (node (ref "C18") (pin "1") (pinfunction "1_1") (pintype "passive"))
      (node (ref "C19") (pin "1") (pinfunction "1_1") (pintype "passive"))
      (node (ref "C2") (pin "1") (pinfunction "1_1") (pintype "passive"))
      (node (ref "IC1") (pin "108") (pinfunction "VDD-SYS1_108") (pintype "bidirectional"))
      (node (ref "IC1") (pin "126") (pinfunction "VDD-SYS2_126") (pintype "bidirectional"))
      (node (ref "IC1") (pin "19") (pinfunction "VDD-SYS3_19") (pintype "bidirectional"))
      (node (ref "IC1") (pin "58") (pinfunction "VDD-SYS4_58") (pintype "bidirectional"))
      (node (ref "IC1") (pin "64") (pinfunction "VDD-SYS5_64") (pintype "bidirectional"))
      (node (ref "IC1") (pin "80") (pinfunction "VDD-SYS0_80") (pintype "bidirectional"))
    )
    (net (code "98") (name "VINT") (class "Default")
      (node (ref "C40") (pin "1") (pinfunction "1_1") (pintype "passive"))
      (node (ref "IC4") (pin "26") (pinfunction "VINT_26") (pintype "bidirectional"))
      (node (ref "IC4") (pin "27") (pinfunction "LDO1SET_27") (pintype "bidirectional"))
    )
    (net (code "99") (name "VREF") (class "Default")
      (node (ref "C43") (pin "1") (pinfunction "1_1") (pintype "passive"))
      (node (ref "IC4") (pin "24") (pinfunction "VREF_24") (pintype "bidirectional"))
    )
    (net (code "100") (name "VRTC") (class "Default")
      (node (ref "IC1") (pin "97") (pinfunction "VCC-RTC_VIO_97") (pintype "bidirectional"))
    )
    (net (code "101") (name "WL_HOST_WAKE") (class "Default")
      (node (ref "U3") (pin "13") (pinfunction "WL_HOST_WAKE_13") (pintype "bidirectional"))
    )
    (net (code "102") (name "unconnected-(IC1C-VCC-PE0-Pad12)") (class "Default")
      (node (ref "IC1") (pin "12") (pinfunction "VCC-PE0_12") (pintype "bidirectional"))
    )
    (net (code "103") (name "unconnected-(IC1C-VCC-PE1-Pad29)") (class "Default")
      (node (ref "IC1") (pin "29") (pinfunction "VCC-PE1_29") (pintype "bidirectional"))
    )
    (net (code "104") (name "unconnected-(IC1C-VCC-RTC-Pad98)") (class "Default")
      (node (ref "IC1") (pin "98") (pinfunction "VCC-RTC_98") (pintype "bidirectional"))
    )
    (net (code "105") (name "unconnected-(IC1E-PB0-Pad39)") (class "Default")
      (node (ref "IC1") (pin "39") (pinfunction "PB0_39") (pintype "bidirectional"))
    )
    (net (code "106") (name "unconnected-(IC1E-PB1-Pad40)") (class "Default")
      (node (ref "IC1") (pin "40") (pinfunction "PB1_40") (pintype "bidirectional"))
    )
    (net (code "107") (name "unconnected-(IC1E-PB2-Pad41)") (class "Default")
      (node (ref "IC1") (pin "41") (pinfunction "PB2_41") (pintype "bidirectional"))
    )
    (net (code "108") (name "unconnected-(IC1E-PB3-Pad42)") (class "Default")
      (node (ref "IC1") (pin "42") (pinfunction "PB3_42") (pintype "bidirectional"))
    )
    (net (code "109") (name "unconnected-(IC1E-PB4-Pad43)") (class "Default")
      (node (ref "IC1") (pin "43") (pinfunction "PB4_43") (pintype "bidirectional"))
    )
    (net (code "110") (name "unconnected-(IC1E-PB5-Pad44)") (class "Default")
      (node (ref "IC1") (pin "44") (pinfunction "PB5_44") (pintype "bidirectional"))
    )
    (net (code "111") (name "unconnected-(IC1G-PE0-Pad37)") (class "Default")
      (node (ref "IC1") (pin "37") (pinfunction "PE0_37") (pintype "bidirectional"))
    )
    (net (code "112") (name "unconnected-(IC1G-PE1-Pad36)") (class "Default")
      (node (ref "IC1") (pin "36") (pinfunction "PE1_36") (pintype "bidirectional"))
    )
    (net (code "113") (name "unconnected-(IC1G-PE2-Pad35)") (class "Default")
      (node (ref "IC1") (pin "35") (pinfunction "PE2_35") (pintype "bidirectional"))
    )
    (net (code "114") (name "unconnected-(IC1G-PE3-Pad34)") (class "Default")
      (node (ref "IC1") (pin "34") (pinfunction "PE3_34") (pintype "bidirectional"))
    )
    (net (code "115") (name "unconnected-(IC1G-PE4-Pad33)") (class "Default")
      (node (ref "IC1") (pin "33") (pinfunction "PE4_33") (pintype "bidirectional"))
    )
    (net (code "116") (name "unconnected-(IC1G-PE5-Pad32)") (class "Default")
      (node (ref "IC1") (pin "32") (pinfunction "PE5_32") (pintype "bidirectional"))
    )
    (net (code "117") (name "unconnected-(IC1G-PE6-Pad31)") (class "Default")
      (node (ref "IC1") (pin "31") (pinfunction "PE6_31") (pintype "bidirectional"))
    )
    (net (code "118") (name "unconnected-(IC1G-PE7-Pad30)") (class "Default")
      (node (ref "IC1") (pin "30") (pinfunction "PE7_30") (pintype "bidirectional"))
    )
    (net (code "119") (name "unconnected-(IC1G-PE8-Pad28)") (class "Default")
      (node (ref "IC1") (pin "28") (pinfunction "PE8_28") (pintype "bidirectional"))
    )
    (net (code "120") (name "unconnected-(IC1G-PE9-Pad27)") (class "Default")
      (node (ref "IC1") (pin "27") (pinfunction "PE9_27") (pintype "bidirectional"))
    )
    (net (code "121") (name "unconnected-(IC1G-PE10-Pad24)") (class "Default")
      (node (ref "IC1") (pin "24") (pinfunction "PE10_24") (pintype "bidirectional"))
    )
    (net (code "122") (name "unconnected-(IC1G-PE11-Pad23)") (class "Default")
      (node (ref "IC1") (pin "23") (pinfunction "PE11_23") (pintype "bidirectional"))
    )
    (net (code "123") (name "unconnected-(IC1G-PE12-Pad22)") (class "Default")
      (node (ref "IC1") (pin "22") (pinfunction "PE12_22") (pintype "bidirectional"))
    )
    (net (code "124") (name "unconnected-(IC1G-PE13-Pad18)") (class "Default")
      (node (ref "IC1") (pin "18") (pinfunction "PE13_18") (pintype "bidirectional"))
    )
    (net (code "125") (name "unconnected-(IC1G-PE14-Pad17)") (class "Default")
      (node (ref "IC1") (pin "17") (pinfunction "PE14_17") (pintype "bidirectional"))
    )
    (net (code "126") (name "unconnected-(IC1G-PE15-Pad16)") (class "Default")
      (node (ref "IC1") (pin "16") (pinfunction "PE15_16") (pintype "bidirectional"))
    )
    (net (code "127") (name "unconnected-(IC1G-PE16-Pad15)") (class "Default")
      (node (ref "IC1") (pin "15") (pinfunction "PE16_15") (pintype "bidirectional"))
    )
    (net (code "128") (name "unconnected-(IC1G-PE17-Pad14)") (class "Default")
      (node (ref "IC1") (pin "14") (pinfunction "PE17_14") (pintype "bidirectional"))
    )
    (net (code "129") (name "unconnected-(IC1G-PE18-Pad13)") (class "Default")
      (node (ref "IC1") (pin "13") (pinfunction "PE18_13") (pintype "bidirectional"))
    )
    (net (code "130") (name "unconnected-(IC1G-PE19-Pad11)") (class "Default")
      (node (ref "IC1") (pin "11") (pinfunction "PE19_11") (pintype "bidirectional"))
    )
    (net (code "131") (name "unconnected-(IC1G-PE20-Pad10)") (class "Default")
      (node (ref "IC1") (pin "10") (pinfunction "PE20_10") (pintype "bidirectional"))
    )
    (net (code "132") (name "unconnected-(IC1G-PE21-Pad9)") (class "Default")
      (node (ref "IC1") (pin "9") (pinfunction "PE21_9") (pintype "bidirectional"))
    )
    (net (code "133") (name "unconnected-(IC1G-PE22-Pad8)") (class "Default")
      (node (ref "IC1") (pin "8") (pinfunction "PE22_8") (pintype "bidirectional"))
    )
    (net (code "134") (name "unconnected-(IC1G-PE23-Pad7)") (class "Default")
      (node (ref "IC1") (pin "7") (pinfunction "PE23_7") (pintype "bidirectional"))
    )
    (net (code "135") (name "unconnected-(IC1G-PE24-Pad6)") (class "Default")
      (node (ref "IC1") (pin "6") (pinfunction "PE24_6") (pintype "bidirectional"))
    )
    (net (code "136") (name "unconnected-(IC1K-ANA_HBIAS-Pad119)") (class "Default")
      (node (ref "IC1") (pin "119") (pinfunction "ANA_HBIAS_119") (pintype "bidirectional"))
    )
    (net (code "137") (name "unconnected-(IC1K-ANA_HPCOM-Pad125)") (class "Default")
      (node (ref "IC1") (pin "125") (pinfunction "ANA_HPCOM_125") (pintype "bidirectional"))
    )
    (net (code "138") (name "unconnected-(IC1K-ANA_HPCOMFB-Pad124)") (class "Default")
      (node (ref "IC1") (pin "124") (pinfunction "ANA_HPCOMFB_124") (pintype "bidirectional"))
    )
    (net (code "139") (name "unconnected-(IC1K-ANA_HPOUTL-Pad121)") (class "Default")
      (node (ref "IC1") (pin "121") (pinfunction "ANA_HPOUTL_121") (pintype "bidirectional"))
    )
    (net (code "140") (name "unconnected-(IC1K-ANA_HPOUTR-Pad120)") (class "Default")
      (node (ref "IC1") (pin "120") (pinfunction "ANA_HPOUTR_120") (pintype "bidirectional"))
    )
    (net (code "141") (name "unconnected-(IC1K-ANA_HPVCCBP-Pad123)") (class "Default")
      (node (ref "IC1") (pin "123") (pinfunction "ANA_HPVCCBP_123") (pintype "bidirectional"))
    )
    (net (code "142") (name "unconnected-(IC1K-ANA_LRADC-Pad112)") (class "Default")
      (node (ref "IC1") (pin "112") (pinfunction "ANA_LRADC_112") (pintype "bidirectional"))
    )
    (net (code "143") (name "unconnected-(IC1K-ANA_MICIN1N-Pad114)") (class "Default")
      (node (ref "IC1") (pin "114") (pinfunction "ANA_MICIN1N_114") (pintype "bidirectional"))
    )
    (net (code "144") (name "unconnected-(IC1K-ANA_MICIN1P-Pad113)") (class "Default")
      (node (ref "IC1") (pin "113") (pinfunction "ANA_MICIN1P_113") (pintype "bidirectional"))
    )
    (net (code "145") (name "unconnected-(IC1K-ANA_VRA1-Pad117)") (class "Default")
      (node (ref "IC1") (pin "117") (pinfunction "ANA_VRA1_117") (pintype "bidirectional"))
    )
    (net (code "146") (name "unconnected-(IC1K-ANA_VRA2-Pad118)") (class "Default")
      (node (ref "IC1") (pin "118") (pinfunction "ANA_VRA2_118") (pintype "bidirectional"))
    )
    (net (code "147") (name "unconnected-(IC3-EN-Pad3)") (class "Default")
      (node (ref "IC3") (pin "3") (pinfunction "EN_3") (pintype "bidirectional"))
    )
    (net (code "148") (name "unconnected-(IC4-BACKUP-Pad30)") (class "Default")
      (node (ref "IC4") (pin "30") (pinfunction "BACKUP_30") (pintype "bidirectional"))
    )
    (net (code "149") (name "unconnected-(IC4-CHGLED-Pad36)") (class "Default")
      (node (ref "IC4") (pin "36") (pinfunction "CHGLED_36") (pintype "bidirectional"))
    )
    (net (code "150") (name "unconnected-(S1-Pad1)") (class "Default")
      (node (ref "S1") (pin "1") (pinfunction "1_1") (pintype "passive"))
    )
    (net (code "151") (name "unconnected-(S1-Pad2)") (class "Default")
      (node (ref "S1") (pin "2") (pinfunction "2_2") (pintype "passive"))
    )
    (net (code "152") (name "unconnected-(S1-Pad3)") (class "Default")
      (node (ref "S1") (pin "3") (pinfunction "3_3") (pintype "passive"))
    )
    (net (code "153") (name "unconnected-(S1-Pad4)") (class "Default")
      (node (ref "S1") (pin "4") (pinfunction "4_4") (pintype "passive"))
    )
    (net (code "154") (name "unconnected-(S1-SHIELD-Pad5)") (class "Default")
      (node (ref "S1") (pin "5") (pinfunction "SHIELD_5") (pintype "passive"))
    )
    (net (code "155") (name "unconnected-(S2-2-Pad3)") (class "Default")
      (node (ref "S2") (pin "3") (pinfunction "2_3") (pintype "bidirectional"))
    )
    (net (code "156") (name "unconnected-(S2-C-Pad4)") (class "Default")
      (node (ref "S2") (pin "4") (pinfunction "C_4") (pintype "bidirectional"))
    )
    (net (code "157") (name "unconnected-(S2-G-Pad5)") (class "Default")
      (node (ref "S2") (pin "5") (pinfunction "G_5") (pintype "bidirectional"))
    )
    (net (code "158") (name "unconnected-(S2-Pad1)") (class "Default")
      (node (ref "S2") (pin "1") (pinfunction "1_1") (pintype "bidirectional"))
    )
    (net (code "159") (name "unconnected-(S2-T-Pad2)") (class "Default")
      (node (ref "S2") (pin "2") (pinfunction "T_2") (pintype "bidirectional"))
    )
    (net (code "160") (name "unconnected-(SV1-Pad5)") (class "Default")
      (node (ref "SV1") (pin "5") (pinfunction "5_5") (pintype "passive"))
    )
    (net (code "161") (name "unconnected-(SV1-Pad6)") (class "Default")
      (node (ref "SV1") (pin "6") (pinfunction "6_6") (pintype "passive"))
    )
    (net (code "162") (name "unconnected-(SV1-Pad8)") (class "Default")
      (node (ref "SV1") (pin "8") (pinfunction "8_8") (pintype "passive"))
    )
    (net (code "163") (name "unconnected-(SV1-Pad9)") (class "Default")
      (node (ref "SV1") (pin "9") (pinfunction "9_9") (pintype "passive"))
    )
    (net (code "164") (name "unconnected-(SV1-Pad10)") (class "Default")
      (node (ref "SV1") (pin "10") (pinfunction "10_10") (pintype "passive"))
    )
    (net (code "165") (name "unconnected-(SV1-Pad11)") (class "Default")
      (node (ref "SV1") (pin "11") (pinfunction "11_11") (pintype "passive"))
    )
    (net (code "166") (name "unconnected-(SV1-Pad12)") (class "Default")
      (node (ref "SV1") (pin "12") (pinfunction "12_12") (pintype "passive"))
    )
    (net (code "167") (name "unconnected-(SV1-Pad13)") (class "Default")
      (node (ref "SV1") (pin "13") (pinfunction "13_13") (pintype "passive"))
    )
    (net (code "168") (name "unconnected-(SV1-Pad14)") (class "Default")
      (node (ref "SV1") (pin "14") (pinfunction "14_14") (pintype "passive"))
    )
    (net (code "169") (name "unconnected-(SV1-Pad15)") (class "Default")
      (node (ref "SV1") (pin "15") (pinfunction "15_15") (pintype "passive"))
    )
    (net (code "170") (name "unconnected-(SV1-Pad16)") (class "Default")
      (node (ref "SV1") (pin "16") (pinfunction "16_16") (pintype "passive"))
    )
    (net (code "171") (name "unconnected-(SV1-Pad17)") (class "Default")
      (node (ref "SV1") (pin "17") (pinfunction "17_17") (pintype "passive"))
    )
    (net (code "172") (name "unconnected-(SV1-Pad18)") (class "Default")
      (node (ref "SV1") (pin "18") (pinfunction "18_18") (pintype "passive"))
    )
    (net (code "173") (name "unconnected-(SV1-Pad19)") (class "Default")
      (node (ref "SV1") (pin "19") (pinfunction "19_19") (pintype "passive"))
    )
    (net (code "174") (name "unconnected-(SV1-Pad20)") (class "Default")
      (node (ref "SV1") (pin "20") (pinfunction "20_20") (pintype "passive"))
    )
    (net (code "175") (name "unconnected-(SV1-Pad21)") (class "Default")
      (node (ref "SV1") (pin "21") (pinfunction "21_21") (pintype "passive"))
    )
    (net (code "176") (name "unconnected-(SV1-Pad22)") (class "Default")
      (node (ref "SV1") (pin "22") (pinfunction "22_22") (pintype "passive"))
    )
    (net (code "177") (name "unconnected-(SV1-Pad23)") (class "Default")
      (node (ref "SV1") (pin "23") (pinfunction "23_23") (pintype "passive"))
    )
    (net (code "178") (name "unconnected-(SV1-Pad24)") (class "Default")
      (node (ref "SV1") (pin "24") (pinfunction "24_24") (pintype "passive"))
    )
    (net (code "179") (name "unconnected-(SV1-Pad25)") (class "Default")
      (node (ref "SV1") (pin "25") (pinfunction "25_25") (pintype "passive"))
    )
    (net (code "180") (name "unconnected-(SV1-Pad26)") (class "Default")
      (node (ref "SV1") (pin "26") (pinfunction "26_26") (pintype "passive"))
    )
    (net (code "181") (name "unconnected-(SV1-Pad27)") (class "Default")
      (node (ref "SV1") (pin "27") (pinfunction "27_27") (pintype "passive"))
    )
    (net (code "182") (name "unconnected-(SV1-Pad28)") (class "Default")
      (node (ref "SV1") (pin "28") (pinfunction "28_28") (pintype "passive"))
    )
    (net (code "183") (name "unconnected-(SV1-Pad29)") (class "Default")
      (node (ref "SV1") (pin "29") (pinfunction "29_29") (pintype "passive"))
    )
    (net (code "184") (name "unconnected-(SV1-Pad30)") (class "Default")
      (node (ref "SV1") (pin "30") (pinfunction "30_30") (pintype "passive"))
    )
    (net (code "185") (name "unconnected-(SV1-Pad31)") (class "Default")
      (node (ref "SV1") (pin "31") (pinfunction "31_31") (pintype "passive"))
    )
    (net (code "186") (name "unconnected-(SV1-Pad32)") (class "Default")
      (node (ref "SV1") (pin "32") (pinfunction "32_32") (pintype "passive"))
    )
    (net (code "187") (name "unconnected-(SV1-Pad33)") (class "Default")
      (node (ref "SV1") (pin "33") (pinfunction "33_33") (pintype "passive"))
    )
    (net (code "188") (name "unconnected-(SV1-Pad34)") (class "Default")
      (node (ref "SV1") (pin "34") (pinfunction "34_34") (pintype "passive"))
    )
    (net (code "189") (name "unconnected-(SV1-Pad35)") (class "Default")
      (node (ref "SV1") (pin "35") (pinfunction "35_35") (pintype "passive"))
    )
    (net (code "190") (name "unconnected-(SV1-Pad36)") (class "Default")
      (node (ref "SV1") (pin "36") (pinfunction "36_36") (pintype "passive"))
    )
    (net (code "191") (name "unconnected-(U3-BT_HOST_WAKE-Pad7)") (class "Default")
      (node (ref "U3") (pin "7") (pinfunction "BT_HOST_WAKE_7") (pintype "bidirectional"))
    )
    (net (code "192") (name "unconnected-(U3-BT_RST_N-Pad34)") (class "Default")
      (node (ref "U3") (pin "34") (pinfunction "BT_RST_N_34") (pintype "bidirectional"))
    )
    (net (code "193") (name "unconnected-(U3-BT_WAKE-Pad6)") (class "Default")
      (node (ref "U3") (pin "6") (pinfunction "BT_WAKE_6") (pintype "bidirectional"))
    )
    (net (code "194") (name "unconnected-(U3-BT_XTAL_IN-Pad37)") (class "Default")
      (node (ref "U3") (pin "37") (pinfunction "BT_XTAL_IN_37") (pintype "bidirectional"))
    )
    (net (code "195") (name "unconnected-(U3-BT_XTAL_OUT-Pad38)") (class "Default")
      (node (ref "U3") (pin "38") (pinfunction "BT_XTAL_OUT_38") (pintype "bidirectional"))
    )
    (net (code "196") (name "unconnected-(U3-LPO-Pad24)") (class "Default")
      (node (ref "U3") (pin "24") (pinfunction "LPO_24") (pintype "bidirectional"))
    )
    (net (code "197") (name "unconnected-(U3-NC-Pad4)") (class "Default")
      (node (ref "U3") (pin "4") (pinfunction "NC_4") (pintype "bidirectional"))
    )
    (net (code "198") (name "unconnected-(U3-NC-Pad5)") (class "Default")
      (node (ref "U3") (pin "5") (pinfunction "NC_5") (pintype "bidirectional"))
    )
    (net (code "199") (name "unconnected-(U3-NC-Pad8)") (class "Default")
      (node (ref "U3") (pin "8") (pinfunction "NC_8") (pintype "bidirectional"))
    )
    (net (code "200") (name "unconnected-(U3-NC-Pad32)") (class "Default")
      (node (ref "U3") (pin "32") (pinfunction "NC_32") (pintype "bidirectional"))
    )
    (net (code "201") (name "unconnected-(U3-NC-Pad35)") (class "Default")
      (node (ref "U3") (pin "35") (pinfunction "NC_35") (pintype "bidirectional"))
    )
    (net (code "202") (name "unconnected-(U3-NC-Pad39)") (class "Default")
      (node (ref "U3") (pin "39") (pinfunction "NC_39") (pintype "bidirectional"))
    )
    (net (code "203") (name "unconnected-(U3-NC-Pad40)") (class "Default")
      (node (ref "U3") (pin "40") (pinfunction "NC_40") (pintype "bidirectional"))
    )
    (net (code "204") (name "unconnected-(U3-PCM_CLK-Pad26)") (class "Default")
      (node (ref "U3") (pin "26") (pinfunction "PCM_CLK_26") (pintype "bidirectional"))
    )
    (net (code "205") (name "unconnected-(U3-PCM_IN-Pad27)") (class "Default")
      (node (ref "U3") (pin "27") (pinfunction "PCM_IN_27") (pintype "bidirectional"))
    )
    (net (code "206") (name "unconnected-(U3-PCM_OUT-Pad25)") (class "Default")
      (node (ref "U3") (pin "25") (pinfunction "PCM_OUT_25") (pintype "bidirectional"))
    )
    (net (code "207") (name "unconnected-(U3-PCM_SYNC-Pad28)") (class "Default")
      (node (ref "U3") (pin "28") (pinfunction "PCM_SYNC_28") (pintype "bidirectional"))
    )
    (net (code "208") (name "unconnected-(U3-TXCO_IN-Pad30)") (class "Default")
      (node (ref "U3") (pin "30") (pinfunction "TXCO_IN_30") (pintype "bidirectional"))
    )
    (net (code "209") (name "unconnected-(U3-UART_CTS_N-Pad44)") (class "Default")
      (node (ref "U3") (pin "44") (pinfunction "UART_CTS_N_44") (pintype "bidirectional"))
    )
    (net (code "210") (name "unconnected-(U3-UART_RTS_N-Pad41)") (class "Default")
      (node (ref "U3") (pin "41") (pinfunction "UART_RTS_N_41") (pintype "bidirectional"))
    )
    (net (code "211") (name "unconnected-(U3-UART_RXD-Pad43)") (class "Default")
      (node (ref "U3") (pin "43") (pinfunction "UART_RXD_43") (pintype "bidirectional"))
    )
    (net (code "212") (name "unconnected-(U3-UART_TXD-Pad42)") (class "Default")
      (node (ref "U3") (pin "42") (pinfunction "UART_TXD_42") (pintype "bidirectional"))
    )
    (net (code "213") (name "unconnected-(U3-VBAT-Pad9)") (class "Default")
      (node (ref "U3") (pin "9") (pinfunction "VBAT_9") (pintype "bidirectional"))
    )
    (net (code "214") (name "unconnected-(U3-VDDIO-Pad22)") (class "Default")
      (node (ref "U3") (pin "22") (pinfunction "VDDIO_22") (pintype "bidirectional"))
    )
    (net (code "215") (name "unconnected-(U3-VIN_LDO-Pad23)") (class "Default")
      (node (ref "U3") (pin "23") (pinfunction "VIN_LDO_23") (pintype "bidirectional"))
    )
    (net (code "216") (name "unconnected-(U3-VIN_LDO_OUT-Pad21)") (class "Default")
      (node (ref "U3") (pin "21") (pinfunction "VIN_LDO_OUT_21") (pintype "bidirectional"))
    )
    (net (code "217") (name "unconnected-(U3-WL_REG_ON-Pad12)") (class "Default")
      (node (ref "U3") (pin "12") (pinfunction "WL_REG_ON_12") (pintype "bidirectional"))
    )
    (net (code "218") (name "unconnected-(U3-WL_VDD_TXCO-Pad29)") (class "Default")
      (node (ref "U3") (pin "29") (pinfunction "WL_VDD_TXCO_29") (pintype "bidirectional"))
    )
    (net (code "219") (name "unconnected-(U3-WL_XTAL_IN-Pad10)") (class "Default")
      (node (ref "U3") (pin "10") (pinfunction "WL_XTAL_IN_10") (pintype "bidirectional"))
    )
    (net (code "220") (name "unconnected-(U3-WL_XTAL_OUT-Pad11)") (class "Default")
      (node (ref "U3") (pin "11") (pinfunction "WL_XTAL_OUT_11") (pintype "bidirectional"))
    )
    (net (code "221") (name "unconnected-(U4-FLG-Pad3)") (class "Default")
      (node (ref "U4") (pin "3") (pinfunction "FLG_3") (pintype "bidirectional"))
    )
    (net (code "222") (name "unconnected-(X1-Pad1)") (class "Default")
      (node (ref "X1") (pin "1") (pinfunction "1_1") (pintype "passive"))
    )
    (net (code "223") (name "unconnected-(X1-Pad2)") (class "Default")
      (node (ref "X1") (pin "2") (pinfunction "2_2") (pintype "passive"))
    )
    (net (code "224") (name "unconnected-(X1-Pad3)") (class "Default")
      (node (ref "X1") (pin "3") (pinfunction "3_3") (pintype "passive"))
    )
    (net (code "225") (name "unconnected-(X1-Pad4)") (class "Default")
      (node (ref "X1") (pin "4") (pinfunction "4_4") (pintype "passive"))
    )
    (net (code "226") (name "unconnected-(X1-Pad5)") (class "Default")
      (node (ref "X1") (pin "5") (pinfunction "5_5") (pintype "passive"))
    )
    (net (code "227") (name "unconnected-(X1-Pad6)") (class "Default")
      (node (ref "X1") (pin "6") (pinfunction "6_6") (pintype "passive"))
    )
    (net (code "228") (name "unconnected-(X1-Pad7)") (class "Default")
      (node (ref "X1") (pin "7") (pinfunction "7_7") (pintype "passive"))
    )
    (net (code "229") (name "unconnected-(X1-Pad8)") (class "Default")
      (node (ref "X1") (pin "8") (pinfunction "8_8") (pintype "passive"))
    )
    (net (code "230") (name "unconnected-(X1-Pad9)") (class "Default")
      (node (ref "X1") (pin "9") (pinfunction "9_9") (pintype "passive"))
    )
    (net (code "231") (name "unconnected-(X1-Pad10)") (class "Default")
      (node (ref "X1") (pin "10") (pinfunction "10_10") (pintype "passive"))
    )
    (net (code "232") (name "unconnected-(X1-Pad11)") (class "Default")
      (node (ref "X1") (pin "11") (pinfunction "11_11") (pintype "passive"))
    )
    (net (code "233") (name "unconnected-(X1-Pad12)") (class "Default")
      (node (ref "X1") (pin "12") (pinfunction "12_12") (pintype "passive"))
    )
    (net (code "234") (name "unconnected-(X1-Pad13)") (class "Default")
      (node (ref "X1") (pin "13") (pinfunction "13_13") (pintype "passive"))
    )
    (net (code "235") (name "unconnected-(X1-Pad14)") (class "Default")
      (node (ref "X1") (pin "14") (pinfunction "14_14") (pintype "passive"))
    )
    (net (code "236") (name "unconnected-(X1-Pad15)") (class "Default")
      (node (ref "X1") (pin "15") (pinfunction "15_15") (pintype "passive"))
    )
    (net (code "237") (name "~{BUS_RST}") (class "Default")
      (node (ref "IC1") (pin "99") (pinfunction "RESET_99") (pintype "bidirectional"))
      (node (ref "IC4") (pin "25") (pinfunction "POWOK_25") (pintype "bidirectional"))
      (node (ref "R23") (pin "1") (pinfunction "1_1") (pintype "passive"))
      (node (ref "SV1") (pin "7") (pinfunction "7_7") (pintype "passive"))
    )
  )
)
